# 02-Insence_interface.net
KiCad netlist of a schematic drawn in Altium Designer
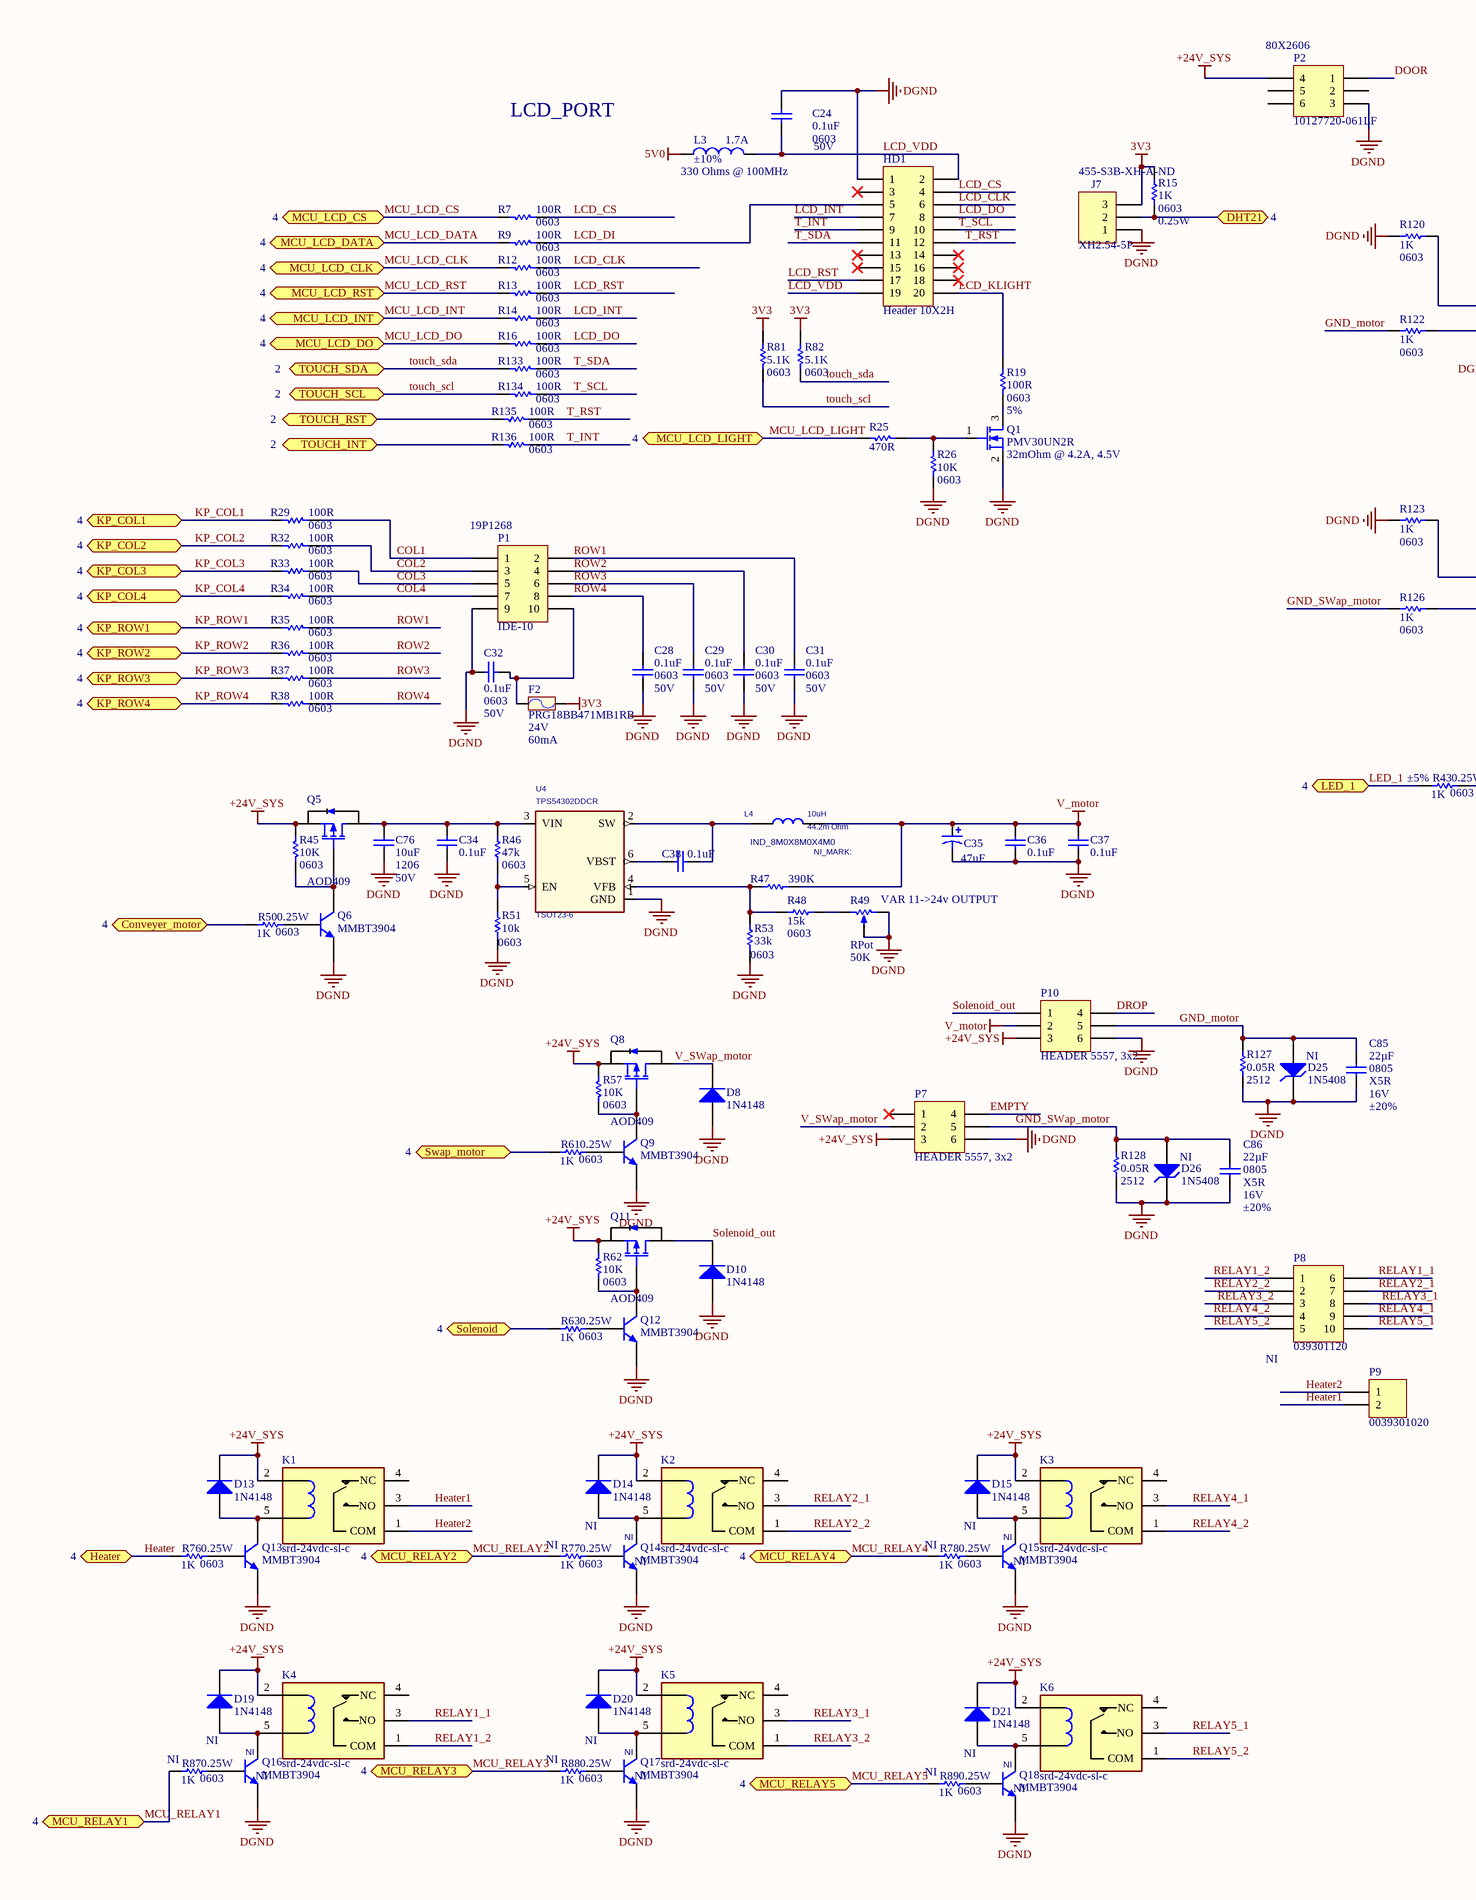
[diagram p0: 02-Insence_interface.SchDoc, left]
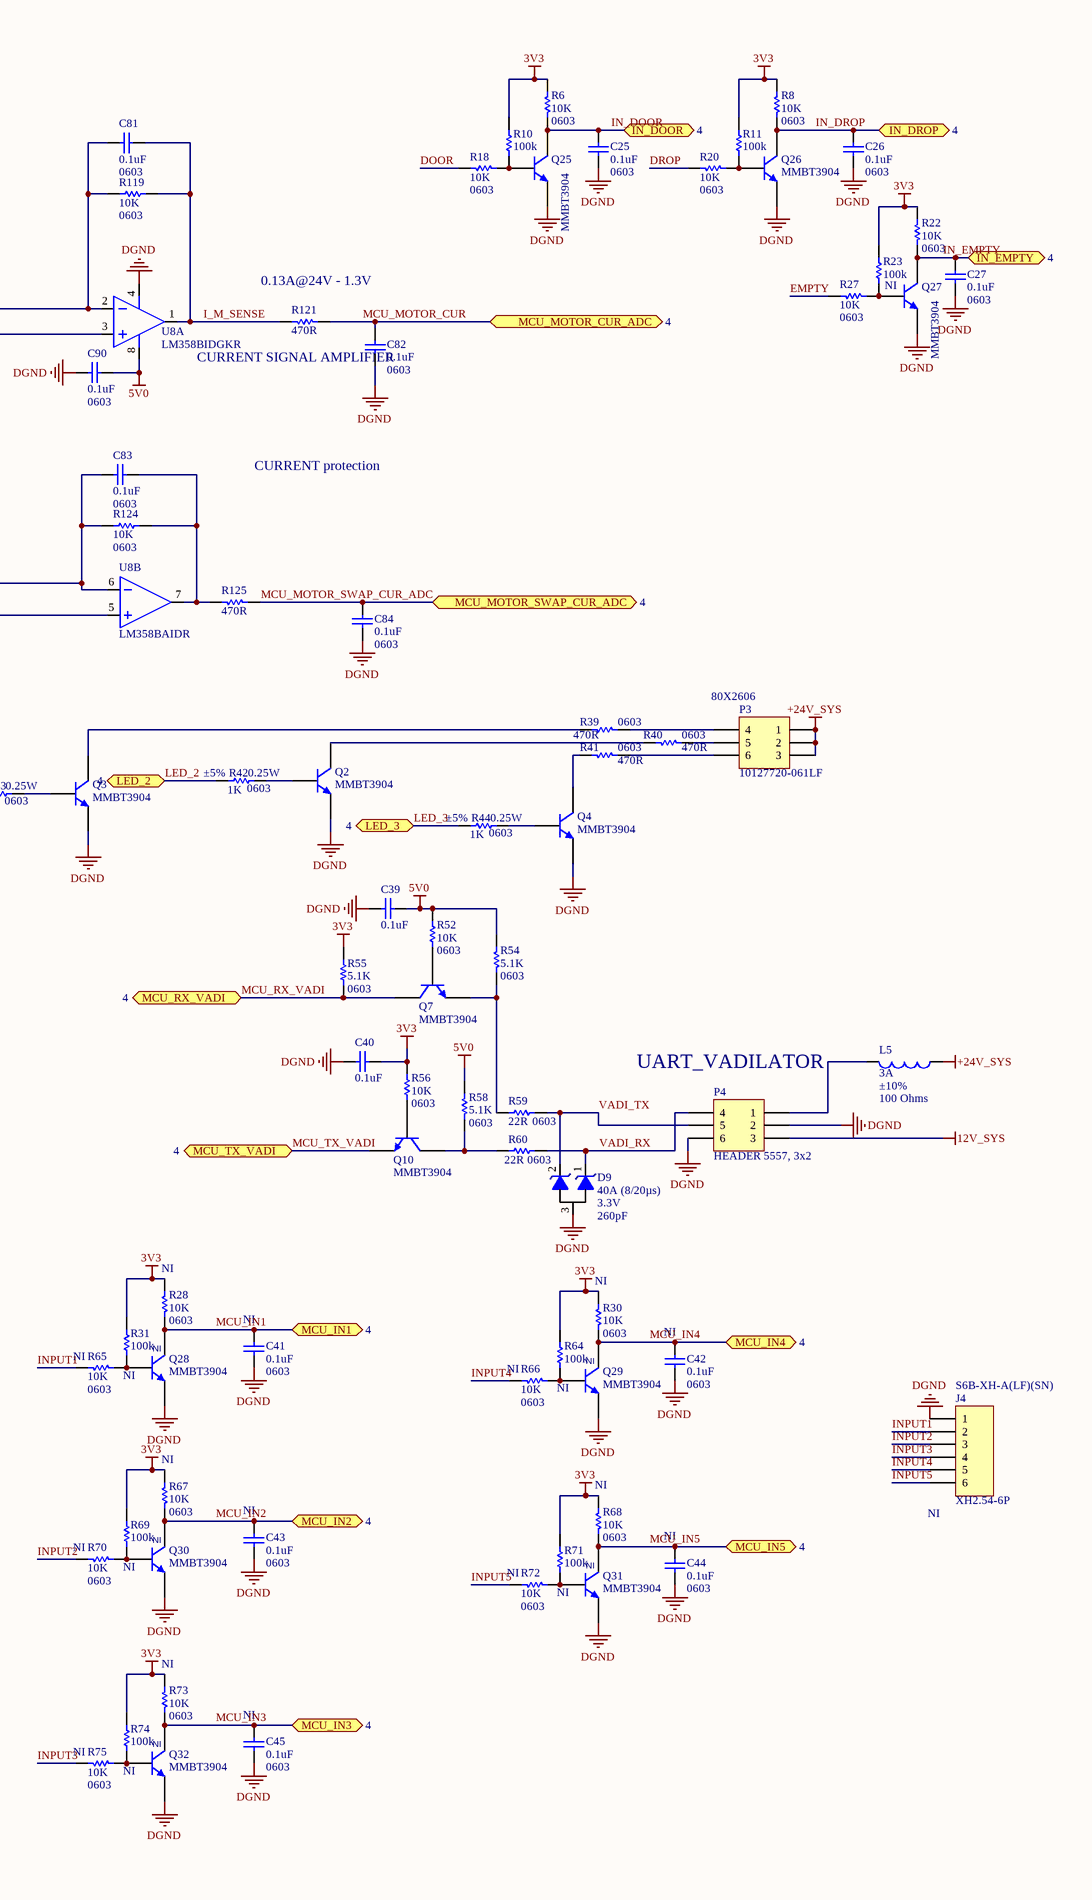
[diagram p1: 02-Insence_interface.SchDoc, right]

(export (version "E")
  (design (tool "Eeschema 10.0.6"))
  (components
    (comp (ref "C24")
      (value "0.1uF")
      (footprint "0603")
      (description "CAP CER 0.1UF 50V X7R 0603")
      (fields
        (field (name "MANUFACTURER1_PART#") "CL10B104KB8NNNC")
        (field (name "VOLTAGE") "50V")
        (field (name "TOLERANCE") "±10%")
      )
      (libsource (lib "thuvien") (part "Cap_0.1uF"))
    )
    (comp (ref "C25")
      (value "0.1uF")
      (footprint "0603")
      (description "CAP CER 0.1UF 50V X7R 0603")
      (fields (field (name "VOLTAGE") "50V") (field (name "TOLERANCE") "±10%"))
      (libsource (lib "Slider") (part "Cap"))
    )
    (comp (ref "C26")
      (value "0.1uF")
      (footprint "0603")
      (description "CAP CER 0.1UF 50V X7R 0603")
      (fields (field (name "VOLTAGE") "50V") (field (name "TOLERANCE") "±10%"))
      (libsource (lib "Slider") (part "Cap"))
    )
    (comp (ref "C27")
      (value "0.1uF")
      (footprint "0603")
      (description "CAP CER 0.1UF 50V X7R 0603")
      (fields (field (name "VOLTAGE") "50V") (field (name "TOLERANCE") "±10%"))
      (libsource (lib "Slider") (part "Cap"))
    )
    (comp (ref "C28")
      (value "0.1uF")
      (footprint "0603")
      (description "CAP CER 0.1UF 50V X7R 0603")
      (fields
        (field (name "MANUFACTURER1_PART#") "CL10B104KB8NNNC")
        (field (name "VOLTAGE") "50V")
        (field (name "TOLERANCE") "±10%")
      )
      (libsource (lib "thuvien") (part "Cap_0.1uF"))
    )
    (comp (ref "C29")
      (value "0.1uF")
      (footprint "0603")
      (description "CAP CER 0.1UF 50V X7R 0603")
      (fields
        (field (name "MANUFACTURER1_PART#") "CL10B104KB8NNNC")
        (field (name "VOLTAGE") "50V")
        (field (name "TOLERANCE") "±10%")
      )
      (libsource (lib "thuvien") (part "Cap_0.1uF"))
    )
    (comp (ref "C30")
      (value "0.1uF")
      (footprint "0603")
      (description "CAP CER 0.1UF 50V X7R 0603")
      (fields
        (field (name "MANUFACTURER1_PART#") "CL10B104KB8NNNC")
        (field (name "VOLTAGE") "50V")
        (field (name "TOLERANCE") "±10%")
      )
      (libsource (lib "thuvien") (part "Cap_0.1uF"))
    )
    (comp (ref "C31")
      (value "0.1uF")
      (footprint "0603")
      (description "CAP CER 0.1UF 50V X7R 0603")
      (fields
        (field (name "MANUFACTURER1_PART#") "CL10B104KB8NNNC")
        (field (name "VOLTAGE") "50V")
        (field (name "TOLERANCE") "±10%")
      )
      (libsource (lib "thuvien") (part "Cap_0.1uF"))
    )
    (comp (ref "C32")
      (value "0.1uF")
      (footprint "0603")
      (description "CAP CER 0.1UF 50V X7R 0603")
      (fields
        (field (name "MANUFACTURER1_PART#") "CL10B104KB8NNNC")
        (field (name "VOLTAGE") "50V")
        (field (name "TOLERANCE") "±10%")
      )
      (libsource (lib "thuvien") (part "Cap_0.1uF"))
    )
    (comp (ref "C34")
      (value "Cap")
      (footprint "0805")
      (description "CAP CER 0.1UF 50V X7R 0603")
      (fields
        (field (name "=VALUE") "0.1uF")
        (field (name "MANUFACTURER1_PART#") "CL10B104KB8NNNC")
        (field (name "PUBLISHER") "Altium Limited")
      )
      (libsource (lib "Miscellaneous Devices") (part "Cap"))
    )
    (comp (ref "C35")
      (value "47uF")
      (footprint "CAP ALUM SMD-D Package 6.3x5.4mm")
      (description "CAP ALUM 47UF 20% 35V SMD")
      (fields
        (field (name "MANUFACTURER1_PART#") "UUR1V470MCL6GS")
        (field (name "MANUFACTURER2_PART#") "EDK476M035A9GAA")
      )
      (libsource (lib "My Library") (part "Cap TANTAN 47UF35V2917"))
    )
    (comp (ref "C36")
      (value "Cap")
      (footprint "0805")
      (description "cap,0805,0.1uF,50V")
      (fields (field (name "=VALUE") "0.1uF") (field (name "PUBLISHER") "Altium Limited"))
      (libsource (lib "Miscellaneous Devices") (part "Cap"))
    )
    (comp (ref "C37")
      (value "Cap")
      (footprint "0805")
      (description "cap,0805,0.1uF,50V")
      (fields (field (name "=VALUE") "0.1uF") (field (name "PUBLISHER") "Altium Limited"))
      (libsource (lib "Miscellaneous Devices") (part "Cap"))
    )
    (comp (ref "C38")
      (value "Cap")
      (footprint "cap 0603")
      (description "CAP CER 0.1UF 50V X7R 0603")
      (fields
        (field (name "=VALUE") "0.1uF")
        (field (name "MANUFACTURER1_PART#") "CL10B104KB8NNNC")
        (field (name "PUBLISHER") "Altium Limited")
      )
      (libsource (lib "Miscellaneous Devices") (part "Cap"))
    )
    (comp (ref "C39")
      (value "0.1uF")
      (footprint "CAP 0603")
      (description "CAP CER 0.1UF 50V X7R 0603")
      (fields (field (name "VOLTAGE") "50V") (field (name "TOLERANCE") "±10%"))
      (libsource (lib "Slider") (part "Cap"))
    )
    (comp (ref "C40")
      (value "0.1uF")
      (footprint "CAP 0603")
      (description "CAP CER 0.1UF 50V X7R 0603")
      (fields (field (name "VOLTAGE") "50V") (field (name "TOLERANCE") "±10%"))
      (libsource (lib "Slider") (part "Cap"))
    )
    (comp (ref "C41")
      (value "0.1uF")
      (footprint "0603")
      (description "CAP CER 0.1UF 50V X7R 0603")
      (fields (field (name "NI_MARK") "NI") (field (name "VOLTAGE") "50V") (field (name "TOLERANCE") "±10%"))
      (libsource (lib "Slider") (part "Cap"))
    )
    (comp (ref "C42")
      (value "0.1uF")
      (footprint "0603")
      (description "CAP CER 0.1UF 50V X7R 0603")
      (fields (field (name "NI_MARK") "NI") (field (name "VOLTAGE") "50V") (field (name "TOLERANCE") "±10%"))
      (libsource (lib "Slider") (part "Cap"))
    )
    (comp (ref "C43")
      (value "0.1uF")
      (footprint "0603")
      (description "CAP CER 0.1UF 50V X7R 0603")
      (fields (field (name "NI_MARK") "NI") (field (name "VOLTAGE") "50V") (field (name "TOLERANCE") "±10%"))
      (libsource (lib "Slider") (part "Cap"))
    )
    (comp (ref "C44")
      (value "0.1uF")
      (footprint "0603")
      (description "CAP CER 0.1UF 50V X7R 0603")
      (fields (field (name "NI_MARK") "NI") (field (name "VOLTAGE") "50V") (field (name "TOLERANCE") "±10%"))
      (libsource (lib "Slider") (part "Cap"))
    )
    (comp (ref "C45")
      (value "0.1uF")
      (footprint "0603")
      (description "CAP CER 0.1UF 50V X7R 0603")
      (fields (field (name "NI_MARK") "NI") (field (name "VOLTAGE") "50V") (field (name "TOLERANCE") "±10%"))
      (libsource (lib "Slider") (part "Cap"))
    )
    (comp (ref "C76")
      (value "10uF")
      (footprint "1206")
      (description "CAP CER 10UF 50V X5R 1206")
      (fields
        (field (name "VOLTAGE") "50V")
        (field (name "TOLERANCE") "±10%")
        (field (name "MANUFACTURER1_PART#") "CL31A106MBHNNNE")
      )
      (libsource (lib "Slider") (part "Cap"))
    )
    (comp (ref "C81")
      (value "0.1uF")
      (footprint "0603")
      (description "CAP CER 0.1UF 50V X7R 0603")
      (fields (field (name "VOLTAGE") "50V") (field (name "TOLERANCE") "±10%"))
      (libsource (lib "Slider") (part "Cap"))
    )
    (comp (ref "C82")
      (value "0.1uF")
      (footprint "0603")
      (description "CAP CER 0.1UF 50V X7R 0603")
      (fields (field (name "VOLTAGE") "50V") (field (name "TOLERANCE") "±10%"))
      (libsource (lib "Slider") (part "Cap"))
    )
    (comp (ref "C83")
      (value "0.1uF")
      (footprint "0603")
      (description "CAP CER 0.1UF 50V X7R 0603")
      (fields (field (name "VOLTAGE") "50V") (field (name "TOLERANCE") "±10%"))
      (libsource (lib "Slider") (part "Cap"))
    )
    (comp (ref "C84")
      (value "0.1uF")
      (footprint "0603")
      (description "CAP CER 0.1UF 50V X7R 0603")
      (fields (field (name "VOLTAGE") "50V") (field (name "TOLERANCE") "±10%"))
      (libsource (lib "Slider") (part "Cap"))
    )
    (comp (ref "C85")
      (value "22µF")
      (footprint "CAP 0805")
      (description "CAP CER 22UF 16V X5R 0805")
      (fields
        (field (name "MANUFACTURER1_PART#") "CL21A226MOCLRNC")
        (field (name "MANUFACTURER2_PART#") "LMK212BBJ226MG-T")
        (field (name "PACKAGE") "0805")
        (field (name "VOLTAGE") "16V")
        (field (name "TOLERANCE") "±20%")
        (field (name "MATERIAL") "X5R")
      )
      (libsource (lib "Full") (part "Cap-NP-100"))
    )
    (comp (ref "C86")
      (value "22µF")
      (footprint "CAP 0805")
      (description "CAP CER 22UF 16V X5R 0805")
      (fields
        (field (name "MANUFACTURER1_PART#") "CL21A226MOCLRNC")
        (field (name "MANUFACTURER2_PART#") "LMK212BBJ226MG-T")
        (field (name "PACKAGE") "0805")
        (field (name "VOLTAGE") "16V")
        (field (name "TOLERANCE") "±20%")
        (field (name "MATERIAL") "X5R")
      )
      (libsource (lib "Full") (part "Cap-NP-100"))
    )
    (comp (ref "C90")
      (value "0.1uF")
      (footprint "0603")
      (description "CAP CER 0.1UF 50V X7R 0603")
      (fields (field (name "VOLTAGE") "50V") (field (name "TOLERANCE") "±10%"))
      (libsource (lib "Slider") (part "Cap"))
    )
    (comp (ref "D8")
      (value "1N4148")
      (footprint "diode_1206")
      (description "DIODE GP 100V 300MA SOD123 10K")
      (fields
        (field (name "MANUFACTURER1_PART#") "1N4148WQ-13-F")
        (field (name "PUBLISHER") "Altium Limited")
      )
      (libsource (lib "Miscellaneous Devices") (part "Diode"))
    )
    (comp (ref "D9")
      (value "SM3.3H-TP")
      (footprint "SOT-23-3")
      (description "3.3V, ESD PROTECTION DEVICES, SO")
      (fields
        (field (name "CURRENT") "40A (8/20µs)")
        (field (name "MANUFACTURER2_PART#") "GSOT03C-E3-08")
        (field (name "POWER") "500W")
        (field (name "VOLTAGE") "3.3V")
        (field (name "JUNCTION CAPACITANCE") "260pF")
      )
      (libsource (lib "My Library") (part "TVS_DUAL_3V3_SOT23"))
    )
    (comp (ref "D10")
      (value "1N4148")
      (footprint "diode_1206")
      (description "DIODE GP 100V 300MA SOD123 10K")
      (fields
        (field (name "MANUFACTURER1_PART#") "1N4148WQ-13-F")
        (field (name "PUBLISHER") "Altium Limited")
      )
      (libsource (lib "Miscellaneous Devices") (part "Diode"))
    )
    (comp (ref "D13")
      (value "1N4148")
      (footprint "diode_1206")
      (description "DIODE GP 100V 300MA SOD123 10K")
      (fields
        (field (name "MANUFACTURER1_PART#") "1N4148WQ-13-F")
        (field (name "PUBLISHER") "Altium Limited")
      )
      (libsource (lib "Miscellaneous Devices") (part "Diode"))
    )
    (comp (ref "D14")
      (value "1N4148")
      (footprint "diode_1206")
      (description "DIODE GP 100V 300MA SOD123 10K")
      (fields
        (field (name "MANUFACTURER1_PART#") "1N4148WQ-13-F")
        (field (name "NI_MARK") "NI")
        (field (name "PUBLISHER") "Altium Limited")
      )
      (libsource (lib "Miscellaneous Devices") (part "Diode"))
    )
    (comp (ref "D15")
      (value "1N4148")
      (footprint "diode_1206")
      (description "DIODE GP 100V 300MA SOD123 10K")
      (fields
        (field (name "MANUFACTURER1_PART#") "1N4148WQ-13-F")
        (field (name "NI_MARK") "NI")
        (field (name "PUBLISHER") "Altium Limited")
      )
      (libsource (lib "Miscellaneous Devices") (part "Diode"))
    )
    (comp (ref "D19")
      (value "1N4148")
      (footprint "diode_1206")
      (description "DIODE GP 100V 300MA SOD123 10K")
      (fields
        (field (name "MANUFACTURER1_PART#") "1N4148WQ-13-F")
        (field (name "NI_MARK") "NI")
        (field (name "PUBLISHER") "Altium Limited")
      )
      (libsource (lib "Miscellaneous Devices") (part "Diode"))
    )
    (comp (ref "D20")
      (value "1N4148")
      (footprint "diode_1206")
      (description "DIODE GP 100V 300MA SOD123 10K")
      (fields
        (field (name "MANUFACTURER1_PART#") "1N4148WQ-13-F")
        (field (name "NI_MARK") "NI")
        (field (name "PUBLISHER") "Altium Limited")
      )
      (libsource (lib "Miscellaneous Devices") (part "Diode"))
    )
    (comp (ref "D21")
      (value "1N4148")
      (footprint "diode_1206")
      (description "DIODE GP 100V 300MA SOD123 10K")
      (fields
        (field (name "MANUFACTURER1_PART#") "1N4148WQ-13-F")
        (field (name "NI_MARK") "NI")
        (field (name "PUBLISHER") "Altium Limited")
      )
      (libsource (lib "Miscellaneous Devices") (part "Diode"))
    )
    (comp (ref "D25")
      (value "1N5408")
      (footprint "SMB")
      (description "TVS DIODE 30V 50.82V DO214AB")
      (fields (field (name "MANUFACTURER1_PART#") "S3MHE3_A/I") (field (name "NI_MARK") "NI"))
      (libsource (lib "My Library") (part "Diode Zener"))
    )
    (comp (ref "D26")
      (value "1N5408")
      (footprint "SMB")
      (description "TVS DIODE 30V 50.82V DO214AB")
      (fields (field (name "MANUFACTURER1_PART#") "S3MHE3_A/I") (field (name "NI_MARK") "NI"))
      (libsource (lib "My Library") (part "Diode Zener"))
    )
    (comp (ref "F2")
      (value "PRG18BB471MB1RB")
      (footprint "FB 0603")
      (description "PTC RESET FUSE 24V 10MA 0603")
      (fields (field (name "VOLTAGE - RATED") "24V") (field (name "CURRENT RATING (AMPS)") "60mA"))
      (libsource (lib "power acdc 12v 400mA V05") (part "0875.800MXEP"))
    )
    (comp (ref "HD1")
      (value "Header 10X2H")
      (footprint "IDE_20-RA")
      (description "CONN HEADER R/A 20POS 2.54MM")
      (fields (field (name "MANUFACTURER1_PART#") "61202021721") (field (name "PUBLISHER") "Altium Limited"))
      (libsource (lib "Miscellaneous Connectors") (part "Header 10X2H"))
    )
    (comp (ref "J4")
      (value "XH2.54-6P")
      (footprint "XH2.54-6P-RA")
      (description "CONN HEADER R/A 6POS 2.5MM")
      (fields
        (field (name "SUPPLIER PART NUMBER 1") "S6B-XH-A(LF)(SN)")
        (field (name "MANUFACTURER1_PART#") "S6B-XH-A")
        (field (name "NI_MARK") "NI")
        (field (name "PUBLISHER") "Altium Limited")
      )
      (libsource (lib "Miscellaneous Connectors") (part "Header 6"))
    )
    (comp (ref "J7")
      (value "XH2.54-5P")
      (footprint "XH2.54-3P-RA")
      (description "CONN HEADER R/A 3POS 2.5MM")
      (fields
        (field (name "SUPPLIER PART NUMBER 1") "455-S3B-XH-A-ND")
        (field (name "MANUFACTURER1_PART#") "S3B-XH-A")
        (field (name "PUBLISHER") "Altium Limited")
      )
      (libsource (lib "Miscellaneous Connectors") (part "Header 3"))
    )
    (comp (ref "K1")
      (value "srd-24vdc-sl-c")
      (footprint "Hiendv:srd24vdcslc")
      (description "Relay 24V 10A 5 PIN")
      (libsource (lib "lib") (part "srd-24vdc-sl-c"))
    )
    (comp (ref "K2")
      (value "srd-24vdc-sl-c")
      (footprint "Hiendv:srd24vdcslc")
      (description "Relay 24V 10A 5 PIN")
      (fields (field (name "NI_MARK") "NI"))
      (libsource (lib "lib") (part "srd-24vdc-sl-c"))
    )
    (comp (ref "K3")
      (value "srd-24vdc-sl-c")
      (footprint "Hiendv:srd24vdcslc")
      (description "Relay 24V 10A 5 PIN")
      (fields (field (name "NI_MARK") "NI"))
      (libsource (lib "lib") (part "srd-24vdc-sl-c"))
    )
    (comp (ref "K4")
      (value "srd-24vdc-sl-c")
      (footprint "Hiendv:srd24vdcslc")
      (description "Relay 24V 10A 5 PIN")
      (fields (field (name "NI_MARK") "NI"))
      (libsource (lib "lib") (part "srd-24vdc-sl-c"))
    )
    (comp (ref "K5")
      (value "srd-24vdc-sl-c")
      (footprint "Hiendv:srd24vdcslc")
      (description "Relay 24V 10A 5 PIN")
      (fields (field (name "NI_MARK") "NI"))
      (libsource (lib "lib") (part "srd-24vdc-sl-c"))
    )
    (comp (ref "K6")
      (value "srd-24vdc-sl-c")
      (footprint "Hiendv:srd24vdcslc")
      (description "Relay 24V 10A 5 PIN")
      (fields (field (name "NI_MARK") "NI"))
      (libsource (lib "lib") (part "srd-24vdc-sl-c"))
    )
    (comp (ref "L3")
      (value "330 Ohms @ 100MHz")
      (footprint "FB 0603")
      (description "FERRITE BEAD 330 OHM 0603 1LN")
      (fields
        (field (name "MANUFACTURER1_PART#") "MPZ1608S331ATA00")
        (field (name "MANUFACTURER2_PART#") "BLM18KG331SN1D")
        (field (name "CURRENT") "1.7A")
        (field (name "TOLERANCE") "±10%")
      )
      (libsource (lib "Full") (part "inductor 2.2uF"))
    )
    (comp (ref "L4")
      (value "10uH")
      (footprint "IND 8x8MM")
      (description "IND-SMD;10uH,20%,8x8x4mm,3.1A,44.2mOHM")
      (fields
        (field (name "PACKAGE") "IND_8M0X8M0X4M0")
        (field (name "TOLERANCE") "20%")
        (field (name "MFG1_PART#") "NR8040T100M")
        (field (name "DCR") "44.2m Ohm")
        (field (name "BY") "VINFAST_RD")
      )
      (libsource (lib "*") (part "IND_10uH_3.1A_44.2mOhm_8MX8MX4M"))
    )
    (comp (ref "L5")
      (value "100 Ohms")
      (footprint "FB 0603")
      (description "FERRITE BEAD 100 OHM 0603 1LN")
      (fields
        (field (name "MANUFACTURER1_PART#") "MPZ1608S101ATAH0")
        (field (name "MANUFACTURER2_PART#") "BLM18KG101TN1D")
        (field (name "CURRENT") "3A")
        (field (name "TOLERANCE") "±10%")
      )
      (libsource (lib "Full") (part "inductor 2.2uF"))
    )
    (comp (ref "P1")
      (value "IDE-10")
      (footprint "IDE-10-RA")
      (description "CONN HEADER R/A 10POS 2.54MM")
      (fields
        (field (name "MANUFACTURER1_PART#") "61201021721")
        (field (name "SUPPLIER PART NUMBER 1") "19P1268")
      )
      (libsource (lib "My Library") (part "IDE10"))
    )
    (comp (ref "P2")
      (value "10127720-061LF")
      (footprint "PHM-3x2H 3.0 - RA")
      (description "Header, 3-Pin, Dual row")
      (fields (field (name "SUPPLIER PART NUMBER 1") "80X2606") (field (name "PUBLISHER") "Altium Limited"))
      (libsource (lib "") (part "Header 3X2A_1"))
    )
    (comp (ref "P3")
      (value "10127720-061LF")
      (footprint "PHM-3x2H 3.0 - RA")
      (description "Header, 3-Pin, Dual row")
      (fields (field (name "SUPPLIER PART NUMBER 1") "80X2606") (field (name "PUBLISHER") "Altium Limited"))
      (libsource (lib "") (part "Header 3X2A_1"))
    )
    (comp (ref "P4")
      (value "HEADER 5557, 3x2")
      (footprint "HDR2x3 4_2MM FEMALE TH RA")
      (description "CONN HEADER R/A 6POS 4.2MM")
      (fields (field (name "MANUFACTURER1_PART#") "0039301060") (field (name "PUBLISHER") "Altium Limited"))
      (libsource (lib "") (part "Header 3X2A_1"))
    )
    (comp (ref "P7")
      (value "HEADER 5557, 3x2")
      (footprint "HDR2x3 4_2MM FEMALE TH RA")
      (description "CONN HEADER R/A 6POS 4.2MM")
      (fields (field (name "MANUFACTURER1_PART#") "0039301060") (field (name "PUBLISHER") "Altium Limited"))
      (libsource (lib "Miscellaneous Connectors") (part "Header 3X2A"))
    )
    (comp (ref "P8")
      (value "039301120")
      (footprint "HDR2x5 4_2MM FEMALE TH RA")
      (description "CONN HEADER R/A 10POS 4.2MM")
      (fields (field (name "NI_MARK") "NI") (field (name "PUBLISHER") "Altium Limited"))
      (libsource (lib "Miscellaneous Connectors") (part "Header 5X2A"))
    )
    (comp (ref "P9")
      (value "0039301020")
      (footprint "HDR2x1 4_2MM FEMALE TH RA")
      (description "Header, 2-Pin, Right Angle")
      (fields (field (name "PUBLISHER") "Altium Limited"))
      (libsource (lib "Miscellaneous Connectors") (part "Header 2H"))
    )
    (comp (ref "P10")
      (value "HEADER 5557, 3x2")
      (footprint "HDR2x3 4_2MM FEMALE TH RA")
      (description "CONN HEADER R/A 6POS 4.2MM")
      (fields (field (name "MANUFACTURER1_PART#") "0039301060") (field (name "PUBLISHER") "Altium Limited"))
      (libsource (lib "Miscellaneous Connectors") (part "Header 3X2A"))
    )
    (comp (ref "Q1")
      (value "PMV30UN2R")
      (footprint "SOT-23-3")
      (description "MOSFET N-CH 20V 4.2A SOT23")
      (fields (field (name "RDSON") "32mOhm @ 4.2A, 4.5V"))
      (libsource (lib "VSM_SES-MAIN_REV04B") (part "Si2302DS"))
    )
    (comp (ref "Q2")
      (value "MMBT3904")
      (footprint "SOT-23")
      (description "NPN 200mA 40V 350mW SOT-23 Transistors")
      (libsource (lib "Miscellaneous Devices") (part "NPN"))
    )
    (comp (ref "Q3")
      (value "MMBT3904")
      (footprint "SOT-23")
      (description "NPN 200mA 40V 350mW SOT-23 Transistors")
      (libsource (lib "Miscellaneous Devices") (part "NPN"))
    )
    (comp (ref "Q4")
      (value "MMBT3904")
      (footprint "SOT-23")
      (description "NPN 200mA 40V 350mW SOT-23 Transistors")
      (libsource (lib "Miscellaneous Devices") (part "NPN"))
    )
    (comp (ref "Q5")
      (value "AOD409")
      (footprint "TO-252")
      (description "MOSFET P-CH 60V 26A TO252")
      (fields (field (name "PUBLISHER") "Altium Limited"))
      (libsource (lib "lib") (part "MOSFET-P"))
    )
    (comp (ref "Q6")
      (value "MMBT3904")
      (footprint "SOT-23")
      (description "NPN 200mA 40V 350mW SOT-23 Transistors")
      (libsource (lib "Miscellaneous Devices") (part "NPN"))
    )
    (comp (ref "Q7")
      (value "MMBT3904")
      (footprint "SOT-23")
      (description "NPN 200mA 40V 350mW SOT-23 Transistors")
      (libsource (lib "") (part "NPN_1"))
    )
    (comp (ref "Q8")
      (value "AOD409")
      (footprint "TO-252")
      (description "MOSFET P-CH 60V 26A TO252")
      (fields (field (name "PUBLISHER") "Altium Limited"))
      (libsource (lib "lib") (part "MOSFET-P"))
    )
    (comp (ref "Q9")
      (value "MMBT3904")
      (footprint "SOT-23")
      (description "NPN 200mA 40V 350mW SOT-23 Transistors")
      (libsource (lib "Miscellaneous Devices") (part "NPN"))
    )
    (comp (ref "Q10")
      (value "MMBT3904")
      (footprint "SOT-23")
      (description "NPN 200mA 40V 350mW SOT-23 Transistors")
      (libsource (lib "") (part "NPN_1"))
    )
    (comp (ref "Q11")
      (value "AOD409")
      (footprint "TO-252")
      (description "MOSFET P-CH 60V 26A TO252")
      (fields (field (name "PUBLISHER") "Altium Limited"))
      (libsource (lib "lib") (part "MOSFET-P"))
    )
    (comp (ref "Q12")
      (value "MMBT3904")
      (footprint "SOT-23")
      (description "NPN 200mA 40V 350mW SOT-23 Transistors")
      (libsource (lib "Miscellaneous Devices") (part "NPN"))
    )
    (comp (ref "Q13")
      (value "MMBT3904")
      (footprint "SOT-23")
      (description "NPN 200mA 40V 350mW SOT-23 Transistors")
      (libsource (lib "Miscellaneous Devices") (part "NPN"))
    )
    (comp (ref "Q14")
      (value "MMBT3904")
      (footprint "SOT-23")
      (description "NPN 200mA 40V 350mW SOT-23 Transistors")
      (fields (field (name "NI_MARK") "NI"))
      (libsource (lib "Miscellaneous Devices") (part "NPN"))
    )
    (comp (ref "Q15")
      (value "MMBT3904")
      (footprint "SOT-23")
      (description "NPN 200mA 40V 350mW SOT-23 Transistors")
      (fields (field (name "NI_MARK") "NI"))
      (libsource (lib "Miscellaneous Devices") (part "NPN"))
    )
    (comp (ref "Q16")
      (value "MMBT3904")
      (footprint "SOT-23")
      (description "NPN 200mA 40V 350mW SOT-23 Transistors")
      (fields (field (name "NI_MARK") "NI"))
      (libsource (lib "Miscellaneous Devices") (part "NPN"))
    )
    (comp (ref "Q17")
      (value "MMBT3904")
      (footprint "SOT-23")
      (description "NPN 200mA 40V 350mW SOT-23 Transistors")
      (fields (field (name "NI_MARK") "NI"))
      (libsource (lib "Miscellaneous Devices") (part "NPN"))
    )
    (comp (ref "Q18")
      (value "MMBT3904")
      (footprint "SOT-23")
      (description "NPN 200mA 40V 350mW SOT-23 Transistors")
      (fields (field (name "NI_MARK") "NI"))
      (libsource (lib "Miscellaneous Devices") (part "NPN"))
    )
    (comp (ref "Q25")
      (value "MMBT3904")
      (footprint "SOT-23")
      (description "NPN 200mA 40V 350mW SOT-23 Transistors")
      (libsource (lib "Miscellaneous Devices") (part "NPN"))
    )
    (comp (ref "Q26")
      (value "MMBT3904")
      (footprint "SOT-23")
      (description "NPN 200mA 40V 350mW SOT-23 Transistors")
      (libsource (lib "Miscellaneous Devices") (part "NPN"))
    )
    (comp (ref "Q27")
      (value "MMBT3904")
      (footprint "SOT-23")
      (description "NPN 200mA 40V 350mW SOT-23 Transistors")
      (libsource (lib "Miscellaneous Devices") (part "NPN"))
    )
    (comp (ref "Q28")
      (value "MMBT3904")
      (footprint "SOT-23")
      (description "NPN 200mA 40V 350mW SOT-23 Transistors")
      (fields (field (name "NI_MARK") "NI"))
      (libsource (lib "Miscellaneous Devices") (part "NPN"))
    )
    (comp (ref "Q29")
      (value "MMBT3904")
      (footprint "SOT-23")
      (description "NPN 200mA 40V 350mW SOT-23 Transistors")
      (fields (field (name "NI_MARK") "NI"))
      (libsource (lib "Miscellaneous Devices") (part "NPN"))
    )
    (comp (ref "Q30")
      (value "MMBT3904")
      (footprint "SOT-23")
      (description "NPN 200mA 40V 350mW SOT-23 Transistors")
      (fields (field (name "NI_MARK") "NI"))
      (libsource (lib "Miscellaneous Devices") (part "NPN"))
    )
    (comp (ref "Q31")
      (value "MMBT3904")
      (footprint "SOT-23")
      (description "NPN 200mA 40V 350mW SOT-23 Transistors")
      (fields (field (name "NI_MARK") "NI"))
      (libsource (lib "Miscellaneous Devices") (part "NPN"))
    )
    (comp (ref "Q32")
      (value "MMBT3904")
      (footprint "SOT-23")
      (description "NPN 200mA 40V 350mW SOT-23 Transistors")
      (fields (field (name "NI_MARK") "NI"))
      (libsource (lib "Miscellaneous Devices") (part "NPN"))
    )
    (comp (ref "R6")
      (value "10K")
      (footprint "res 0603")
      (description "RES SMD,10K OHM 5% 1/10W 0603")
      (fields
        (field (name "MANUFACTURER1_PART#") "RMCF0603JT10K0")
        (field (name "MANUFACTURER2_PART#") "R0603J10KKDX")
        (field (name "PCB FOOTPRINT") "0603")
      )
      (libsource (lib "altium-import") (part "root_3_mirrored_Res0.3_"))
    )
    (comp (ref "R7")
      (value "100R")
      (footprint "res 0603")
      (description "RES 100 OHM 5% 1/10W 0603")
      (fields (field (name "MANUFACTURER1_PART#") "RMCF0603JG100R") (field (name "PCB_ FOOTPRINT") "0603"))
      (libsource (lib "thuvien") (part "RES 120 OHM 5% 1/10W 0603"))
    )
    (comp (ref "R8")
      (value "10K")
      (footprint "res 0603")
      (description "RES SMD,10K OHM 5% 1/10W 0603")
      (fields
        (field (name "MANUFACTURER1_PART#") "RMCF0603JT10K0")
        (field (name "MANUFACTURER2_PART#") "R0603J10KKDX")
        (field (name "PCB FOOTPRINT") "0603")
      )
      (libsource (lib "altium-import") (part "root_3_mirrored_Res0.3_"))
    )
    (comp (ref "R9")
      (value "100R")
      (footprint "res 0603")
      (description "RES 100 OHM 5% 1/10W 0603")
      (fields (field (name "MANUFACTURER1_PART#") "RMCF0603JG100R") (field (name "PCB_ FOOTPRINT") "0603"))
      (libsource (lib "thuvien") (part "RES 120 OHM 5% 1/10W 0603"))
    )
    (comp (ref "R10")
      (value "100k")
      (footprint "RES 0603")
      (description "RES 100K OHM 1% 1/10W 0603")
      (fields
        (field (name "MANUFACTURER1_PART#") "RMCF0603FT100K")
        (field (name "Comment") "100k, 0603")
        (field (name "PUBLISHER") "Altium Limited")
      )
      (libsource (lib "Miscellaneous Devices") (part "Res1"))
    )
    (comp (ref "R11")
      (value "100k")
      (footprint "RES 0603")
      (description "RES 100K OHM 1% 1/10W 0603")
      (fields
        (field (name "MANUFACTURER1_PART#") "RMCF0603FT100K")
        (field (name "Comment") "100k, 0603")
        (field (name "PUBLISHER") "Altium Limited")
      )
      (libsource (lib "Miscellaneous Devices") (part "Res1"))
    )
    (comp (ref "R12")
      (value "100R")
      (footprint "res 0603")
      (description "RES 100 OHM 5% 1/10W 0603")
      (fields (field (name "MANUFACTURER1_PART#") "RMCF0603JG100R") (field (name "PCB_ FOOTPRINT") "0603"))
      (libsource (lib "thuvien") (part "RES 120 OHM 5% 1/10W 0603"))
    )
    (comp (ref "R13")
      (value "100R")
      (footprint "res 0603")
      (description "RES 100 OHM 5% 1/10W 0603")
      (fields (field (name "MANUFACTURER1_PART#") "RMCF0603JG100R") (field (name "PCB_ FOOTPRINT") "0603"))
      (libsource (lib "thuvien") (part "RES 120 OHM 5% 1/10W 0603"))
    )
    (comp (ref "R14")
      (value "100R")
      (footprint "res 0603")
      (description "RES 100 OHM 5% 1/10W 0603")
      (fields (field (name "MANUFACTURER1_PART#") "RMCF0603JG100R") (field (name "PCB_ FOOTPRINT") "0603"))
      (libsource (lib "thuvien") (part "RES 120 OHM 5% 1/10W 0603"))
    )
    (comp (ref "R15")
      (value "1K")
      (footprint "res 0603")
      (description "RES SMD,1K OHM,5%,1/10W,0603")
      (fields
        (field (name "MANUFACTURER1_PART#") "RMCF06031K00JNEAC")
        (field (name "MANUFACTURER2_PART#") "R0603J1KTG")
        (field (name "PCB FOOTPRINT") "0603")
        (field (name "POWER") "0.25W")
      )
      (libsource (lib "Full") (part "Res0.3"))
    )
    (comp (ref "R16")
      (value "100R")
      (footprint "res 0603")
      (description "RES 100 OHM 5% 1/10W 0603")
      (fields (field (name "MANUFACTURER1_PART#") "RMCF0603JG100R") (field (name "PCB_ FOOTPRINT") "0603"))
      (libsource (lib "thuvien") (part "RES 120 OHM 5% 1/10W 0603"))
    )
    (comp (ref "R18")
      (value "10K")
      (footprint "res 0603")
      (description "RES SMD,10K OHM 5% 1/10W 0603")
      (fields
        (field (name "MANUFACTURER1_PART#") "RMCF0603JT10K0")
        (field (name "MANUFACTURER2_PART#") "R0603J10KKDX")
        (field (name "PCB FOOTPRINT") "0603")
      )
      (libsource (lib "altium-import") (part "root_2_mirrored_Res0.3_"))
    )
    (comp (ref "R19")
      (value "100R")
      (footprint "res 0603")
      (description "RES 100 OHM 5% 1/10W 0603")
      (fields
        (field (name "MANUFACTURER1_PART#") "RMCF0603JG100R")
        (field (name "PCB_ FOOTPRINT") "0603")
        (field (name "TOLERANCE") "5%")
      )
      (libsource (lib "thuvien") (part "RES 120 OHM 5% 1/10W 0603"))
    )
    (comp (ref "R20")
      (value "10K")
      (footprint "res 0603")
      (description "RES SMD,10K OHM 5% 1/10W 0603")
      (fields
        (field (name "MANUFACTURER1_PART#") "RMCF0603JT10K0")
        (field (name "MANUFACTURER2_PART#") "R0603J10KKDX")
        (field (name "PCB FOOTPRINT") "0603")
      )
      (libsource (lib "altium-import") (part "root_2_mirrored_Res0.3_"))
    )
    (comp (ref "R22")
      (value "10K")
      (footprint "res 0603")
      (description "RES SMD,10K OHM 5% 1/10W 0603")
      (fields
        (field (name "MANUFACTURER1_PART#") "RMCF0603JT10K0")
        (field (name "MANUFACTURER2_PART#") "R0603J10KKDX")
        (field (name "PCB FOOTPRINT") "0603")
      )
      (libsource (lib "altium-import") (part "root_3_mirrored_Res0.3_"))
    )
    (comp (ref "R23")
      (value "100k")
      (footprint "RES 0603")
      (description "RES 100K OHM 1% 1/10W 0603")
      (fields
        (field (name "MANUFACTURER1_PART#") "RMCF0603FT100K")
        (field (name "ASSEMBLY") "NI")
        (field (name "Comment") "100k, 0603")
        (field (name "PUBLISHER") "Altium Limited")
      )
      (libsource (lib "Miscellaneous Devices") (part "Res1"))
    )
    (comp (ref "R25")
      (value "470R")
      (footprint "res 0603")
      (description "RES SMD, 470 OHM 5% 1/8W 0603")
      (fields
        (field (name "MANUFACTURER1_PART#") "RK73B1JTTD471J")
        (field (name "MANUFACTURER2_PART#") "RMCF0603JT470R")
      )
      (libsource (lib "Full") (part "Res0.3"))
    )
    (comp (ref "R26")
      (value "10K")
      (footprint "res 0603")
      (description "RES SMD,10K OHM 5% 1/10W 0603")
      (fields
        (field (name "MANUFACTURER1_PART#") "RMCF0603JT10K0")
        (field (name "MANUFACTURER2_PART#") "R0603J10KKDX")
        (field (name "PCB FOOTPRINT") "0603")
      )
      (libsource (lib "altium-import") (part "root_3_mirrored_Res0.3_"))
    )
    (comp (ref "R27")
      (value "10K")
      (footprint "res 0603")
      (description "RES SMD,10K OHM 5% 1/10W 0603")
      (fields
        (field (name "MANUFACTURER1_PART#") "RMCF0603JT10K0")
        (field (name "MANUFACTURER2_PART#") "R0603J10KKDX")
        (field (name "PCB FOOTPRINT") "0603")
      )
      (libsource (lib "altium-import") (part "root_2_mirrored_Res0.3_"))
    )
    (comp (ref "R28")
      (value "10K")
      (footprint "res 0603")
      (description "RES SMD,10K OHM 5% 1/10W 0603")
      (fields
        (field (name "MANUFACTURER1_PART#") "RMCF0603JT10K0")
        (field (name "MANUFACTURER2_PART#") "R0603J10KKDX")
        (field (name "NI_MARK") "NI")
        (field (name "PCB FOOTPRINT") "0603")
      )
      (libsource (lib "altium-import") (part "root_3_mirrored_Res0.3_"))
    )
    (comp (ref "R29")
      (value "100R")
      (footprint "res 0603")
      (description "RES 100 OHM 5% 1/10W 0603")
      (fields (field (name "MANUFACTURER1_PART#") "RMCF0603JG100R") (field (name "PCB_ FOOTPRINT") "0603"))
      (libsource (lib "thuvien") (part "RES 120 OHM 5% 1/10W 0603"))
    )
    (comp (ref "R30")
      (value "10K")
      (footprint "res 0603")
      (description "RES SMD,10K OHM 5% 1/10W 0603")
      (fields
        (field (name "MANUFACTURER1_PART#") "RMCF0603JT10K0")
        (field (name "MANUFACTURER2_PART#") "R0603J10KKDX")
        (field (name "NI_MARK") "NI")
        (field (name "PCB FOOTPRINT") "0603")
      )
      (libsource (lib "altium-import") (part "root_3_mirrored_Res0.3_"))
    )
    (comp (ref "R31")
      (value "100k")
      (footprint "RES 0603")
      (description "RES 100K OHM 1% 1/10W 0603")
      (fields
        (field (name "MANUFACTURER1_PART#") "RMCF0603FT100K")
        (field (name "NI_MARK") "NI")
        (field (name "Comment") "100k, 0603")
        (field (name "PUBLISHER") "Altium Limited")
      )
      (libsource (lib "Miscellaneous Devices") (part "Res1"))
    )
    (comp (ref "R32")
      (value "100R")
      (footprint "res 0603")
      (description "RES 100 OHM 5% 1/10W 0603")
      (fields (field (name "MANUFACTURER1_PART#") "RMCF0603JG100R") (field (name "PCB_ FOOTPRINT") "0603"))
      (libsource (lib "thuvien") (part "RES 120 OHM 5% 1/10W 0603"))
    )
    (comp (ref "R33")
      (value "100R")
      (footprint "res 0603")
      (description "RES 100 OHM 5% 1/10W 0603")
      (fields (field (name "MANUFACTURER1_PART#") "RMCF0603JG100R") (field (name "PCB_ FOOTPRINT") "0603"))
      (libsource (lib "thuvien") (part "RES 120 OHM 5% 1/10W 0603"))
    )
    (comp (ref "R34")
      (value "100R")
      (footprint "res 0603")
      (description "RES 100 OHM 5% 1/10W 0603")
      (fields (field (name "MANUFACTURER1_PART#") "RMCF0603JG100R") (field (name "PCB_ FOOTPRINT") "0603"))
      (libsource (lib "thuvien") (part "RES 120 OHM 5% 1/10W 0603"))
    )
    (comp (ref "R35")
      (value "100R")
      (footprint "res 0603")
      (description "RES 100 OHM 5% 1/10W 0603")
      (fields (field (name "MANUFACTURER1_PART#") "RMCF0603JG100R") (field (name "PCB_ FOOTPRINT") "0603"))
      (libsource (lib "thuvien") (part "RES 120 OHM 5% 1/10W 0603"))
    )
    (comp (ref "R36")
      (value "100R")
      (footprint "res 0603")
      (description "RES 100 OHM 5% 1/10W 0603")
      (fields (field (name "MANUFACTURER1_PART#") "RMCF0603JG100R") (field (name "PCB_ FOOTPRINT") "0603"))
      (libsource (lib "thuvien") (part "RES 120 OHM 5% 1/10W 0603"))
    )
    (comp (ref "R37")
      (value "100R")
      (footprint "res 0603")
      (description "RES 100 OHM 5% 1/10W 0603")
      (fields (field (name "MANUFACTURER1_PART#") "RMCF0603JG100R") (field (name "PCB_ FOOTPRINT") "0603"))
      (libsource (lib "thuvien") (part "RES 120 OHM 5% 1/10W 0603"))
    )
    (comp (ref "R38")
      (value "100R")
      (footprint "res 0603")
      (description "RES 100 OHM 5% 1/10W 0603")
      (fields (field (name "MANUFACTURER1_PART#") "RMCF0603JG100R") (field (name "PCB_ FOOTPRINT") "0603"))
      (libsource (lib "thuvien") (part "RES 120 OHM 5% 1/10W 0603"))
    )
    (comp (ref "R39")
      (value "470R")
      (footprint "res 0603")
      (description "RES SMD, 470 OHM 5% 1/8W 0603")
      (fields
        (field (name "MANUFACTURER1_PART#") "RK73B1JTTD471J")
        (field (name "MANUFACTURER2_PART#") "RMCF0603JT470R")
        (field (name "PCB FOOTPRINT") "0603")
      )
      (libsource (lib "Full") (part "Res0.3"))
    )
    (comp (ref "R40")
      (value "470R")
      (footprint "res 0603")
      (description "RES SMD, 470 OHM 5% 1/8W 0603")
      (fields
        (field (name "MANUFACTURER1_PART#") "RK73B1JTTD471J")
        (field (name "MANUFACTURER2_PART#") "RMCF0603JT470R")
        (field (name "PCB FOOTPRINT") "0603")
      )
      (libsource (lib "Full") (part "Res0.3"))
    )
    (comp (ref "R41")
      (value "470R")
      (footprint "res 0603")
      (description "RES SMD, 470 OHM 5% 1/8W 0603")
      (fields
        (field (name "MANUFACTURER1_PART#") "RK73B1JTTD471J")
        (field (name "MANUFACTURER2_PART#") "RMCF0603JT470R")
        (field (name "PCB FOOTPRINT") "0603")
      )
      (libsource (lib "Full") (part "Res0.3"))
    )
    (comp (ref "R42")
      (value "1K")
      (footprint "res 0603")
      (description "RES SMD,1K OHM,5%,1/10W,0603")
      (fields
        (field (name "MANUFACTURER1_PART#") "RMCF06031K00JNEAC")
        (field (name "MANUFACTURER2_PART#") "R0603J1KTG")
        (field (name "PCB FOOTPRINT") "0603")
        (field (name "POWER") "0.25W")
        (field (name "TOLERANCE") "±5%")
      )
      (libsource (lib "Full") (part "Res0.3"))
    )
    (comp (ref "R43")
      (value "1K")
      (footprint "res 0603")
      (description "RES SMD,1K OHM,5%,1/10W,0603")
      (fields
        (field (name "MANUFACTURER1_PART#") "RMCF06031K00JNEAC")
        (field (name "MANUFACTURER2_PART#") "R0603J1KTG")
        (field (name "PCB FOOTPRINT") "0603")
        (field (name "POWER") "0.25W")
        (field (name "TOLERANCE") "±5%")
      )
      (libsource (lib "Full") (part "Res0.3"))
    )
    (comp (ref "R44")
      (value "1K")
      (footprint "res 0603")
      (description "RES SMD,1K OHM,5%,1/10W,0603")
      (fields
        (field (name "MANUFACTURER1_PART#") "RMCF06031K00JNEAC")
        (field (name "MANUFACTURER2_PART#") "R0603J1KTG")
        (field (name "PCB FOOTPRINT") "0603")
        (field (name "POWER") "0.25W")
        (field (name "TOLERANCE") "±5%")
      )
      (libsource (lib "Full") (part "Res0.3"))
    )
    (comp (ref "R45")
      (value "10K")
      (footprint "res 0603")
      (description "RES SMD,10K OHM 5% 1/10W 0603")
      (fields
        (field (name "MANUFACTURER1_PART#") "RMCF0603JT10K0")
        (field (name "MANUFACTURER2_PART#") "R0603J10KKDX")
        (field (name "PCB FOOTPRINT") "0603")
      )
      (libsource (lib "altium-import") (part "root_3_mirrored_Res0.3_"))
    )
    (comp (ref "R46")
      (value "47k")
      (footprint "0603")
      (description "RES 47K OHM 5% 1/10W 0603")
      (fields
        (field (name "MANUFACTURER1_PART#") "RMCF0603JT47K0")
        (field (name "Comment") "Res1")
        (field (name "PUBLISHER") "Altium Limited")
      )
      (libsource (lib "Miscellaneous Devices") (part "Res1"))
    )
    (comp (ref "R47")
      (value "390K")
      (footprint "res 0603")
      (description "RES 390K OHM 1% 1/10W 0603")
      (fields
        (field (name "MANUFACTURER1_PART#") "RC0603FR-07390KL")
        (field (name "Comment") "Res1")
        (field (name "PUBLISHER") "Altium Limited")
      )
      (libsource (lib "Miscellaneous Devices") (part "Res1"))
    )
    (comp (ref "R48")
      (value "15k")
      (footprint "0603")
      (description "RES SMD,15K OHM 5% 1/10W 0603")
      (fields
        (field (name "MANUFACTURER1_PART#") "RMCF0603JT15K0")
        (field (name "Comment") "Res1")
        (field (name "PUBLISHER") "Altium Limited")
      )
      (libsource (lib "Miscellaneous Devices") (part "Res1"))
    )
    (comp (ref "R49")
      (value "RPot")
      (footprint "R_POT_RA")
      (description "VR 3006P-1-503")
      (fields
        (field (name "ALTIUM_VALUE") "50K")
        (field (name "MANUFACTURER1_PART#") "3006P-1-503")
        (field (name "PUBLISHER") "Altium Limited")
      )
      (libsource (lib "Miscellaneous Devices") (part "RPot"))
    )
    (comp (ref "R50")
      (value "1K")
      (footprint "res 0603")
      (description "RES SMD,1K OHM,5%,1/10W,0603")
      (fields
        (field (name "MANUFACTURER1_PART#") "RMCF06031K00JNEAC")
        (field (name "MANUFACTURER2_PART#") "R0603J1KTG")
        (field (name "PCB FOOTPRINT") "0603")
        (field (name "POWER") "0.25W")
      )
      (libsource (lib "Full") (part "Res0.3"))
    )
    (comp (ref "R51")
      (value "10k")
      (footprint "0603")
      (description "RES SMD,10K OHM 5% 1/10W 0603")
      (fields
        (field (name "MANUFACTURER1_PART#") "RMCF0603JT10K0")
        (field (name "Comment") "Res1")
        (field (name "PUBLISHER") "Altium Limited")
      )
      (libsource (lib "Miscellaneous Devices") (part "Res1"))
    )
    (comp (ref "R52")
      (value "10K")
      (footprint "res 0603")
      (description "RES SMD,10K OHM 5% 1/10W 0603")
      (fields
        (field (name "MANUFACTURER1_PART#") "RMCF0603JT10K0")
        (field (name "MANUFACTURER2_PART#") "R0603J10KKDX")
        (field (name "PCB FOOTPRINT") "0603")
      )
      (libsource (lib "altium-import") (part "root_3_Res0.3_"))
    )
    (comp (ref "R53")
      (value "33k")
      (footprint "0603")
      (description "RES SMD,33K OHM 5% 1/10W 0603")
      (fields
        (field (name "MANUFACTURER1_PART#") "RMCF0603JT33K0")
        (field (name "Comment") "Res1")
        (field (name "PUBLISHER") "Altium Limited")
      )
      (libsource (lib "Miscellaneous Devices") (part "Res1"))
    )
    (comp (ref "R54")
      (value "5.1K")
      (footprint "res 0603")
      (description "RES SMD 5.1K OHM 1% 1/10W 0603")
      (fields (field (name "MANUFACTURER1_PART#") "RC0603FR-075K1L") (field (name "PCB FOOTPRINT") "0603"))
      (libsource (lib "Full") (part "Res0.3"))
    )
    (comp (ref "R55")
      (value "5.1K")
      (footprint "res 0603")
      (description "RES SMD 5.1K OHM 1% 1/10W 0603")
      (fields (field (name "MANUFACTURER1_PART#") "RC0603FR-075K1L") (field (name "PCB FOOTPRINT") "0603"))
      (libsource (lib "Full") (part "Res0.3"))
    )
    (comp (ref "R56")
      (value "10K")
      (footprint "res 0603")
      (description "RES SMD,10K OHM 5% 1/10W 0603")
      (fields
        (field (name "MANUFACTURER1_PART#") "RMCF0603JT10K0")
        (field (name "MANUFACTURER2_PART#") "R0603J10KKDX")
        (field (name "PCB FOOTPRINT") "0603")
      )
      (libsource (lib "altium-import") (part "root_3_Res0.3_"))
    )
    (comp (ref "R57")
      (value "10K")
      (footprint "res 0603")
      (description "RES SMD,10K OHM 5% 1/10W 0603")
      (fields
        (field (name "MANUFACTURER1_PART#") "RMCF0603JT10K0")
        (field (name "MANUFACTURER2_PART#") "R0603J10KKDX")
        (field (name "PCB FOOTPRINT") "0603")
      )
      (libsource (lib "altium-import") (part "root_3_mirrored_Res0.3_"))
    )
    (comp (ref "R58")
      (value "5.1K")
      (footprint "res 0603")
      (description "RES SMD 5.1K OHM 1% 1/10W 0603")
      (fields (field (name "MANUFACTURER1_PART#") "RC0603FR-075K1L") (field (name "PCB FOOTPRINT") "0603"))
      (libsource (lib "Full") (part "Res0.3"))
    )
    (comp (ref "R59")
      (value "22R")
      (footprint "res 0603")
      (description "RES 22 OHM 5% 1/10W 0603")
      (fields
        (field (name "MANUFACTURER1_PART#") "RC0603JR-0722RL")
        (field (name "MANUFACTURER2_PART#") "RMCF0603JT22R0")
        (field (name "PCB FOOTPRINT") "0603")
      )
      (libsource (lib "Full") (part "Res0.3"))
    )
    (comp (ref "R60")
      (value "22R")
      (footprint "res 0603")
      (description "RES 22 OHM 5% 1/10W 0603")
      (fields
        (field (name "MANUFACTURER1_PART#") "RC0603JR-0722RL")
        (field (name "MANUFACTURER2_PART#") "RMCF0603JT22R0")
        (field (name "PCB FOOTPRINT") "0603")
      )
      (libsource (lib "Full") (part "Res0.3"))
    )
    (comp (ref "R61")
      (value "1K")
      (footprint "res 0603")
      (description "RES SMD,1K OHM,5%,1/10W,0603")
      (fields
        (field (name "MANUFACTURER1_PART#") "RMCF06031K00JNEAC")
        (field (name "MANUFACTURER2_PART#") "R0603J1KTG")
        (field (name "PCB FOOTPRINT") "0603")
        (field (name "POWER") "0.25W")
      )
      (libsource (lib "Full") (part "Res0.3"))
    )
    (comp (ref "R62")
      (value "10K")
      (footprint "res 0603")
      (description "RES SMD,10K OHM 5% 1/10W 0603")
      (fields
        (field (name "MANUFACTURER1_PART#") "RMCF0603JT10K0")
        (field (name "MANUFACTURER2_PART#") "R0603J10KKDX")
        (field (name "PCB FOOTPRINT") "0603")
      )
      (libsource (lib "altium-import") (part "root_3_mirrored_Res0.3_"))
    )
    (comp (ref "R63")
      (value "1K")
      (footprint "res 0603")
      (description "RES SMD,1K OHM,5%,1/10W,0603")
      (fields
        (field (name "MANUFACTURER1_PART#") "RMCF06031K00JNEAC")
        (field (name "MANUFACTURER2_PART#") "R0603J1KTG")
        (field (name "PCB FOOTPRINT") "0603")
        (field (name "POWER") "0.25W")
      )
      (libsource (lib "Full") (part "Res0.3"))
    )
    (comp (ref "R64")
      (value "100k")
      (footprint "RES 0603")
      (description "RES 100K OHM 1% 1/10W 0603")
      (fields
        (field (name "MANUFACTURER1_PART#") "RMCF0603FT100K")
        (field (name "NI_MARK") "NI")
        (field (name "Comment") "100k, 0603")
        (field (name "PUBLISHER") "Altium Limited")
      )
      (libsource (lib "Miscellaneous Devices") (part "Res1"))
    )
    (comp (ref "R65")
      (value "10K")
      (footprint "res 0603")
      (description "RES SMD,10K OHM 5% 1/10W 0603")
      (fields
        (field (name "MANUFACTURER1_PART#") "RMCF0603JT10K0")
        (field (name "MANUFACTURER2_PART#") "R0603J10KKDX")
        (field (name "NI_MARK") "NI")
        (field (name "PCB FOOTPRINT") "0603")
      )
      (libsource (lib "altium-import") (part "root_2_mirrored_Res0.3_"))
    )
    (comp (ref "R66")
      (value "10K")
      (footprint "res 0603")
      (description "RES SMD,10K OHM 5% 1/10W 0603")
      (fields
        (field (name "MANUFACTURER1_PART#") "RMCF0603JT10K0")
        (field (name "MANUFACTURER2_PART#") "R0603J10KKDX")
        (field (name "NI_MARK") "NI")
        (field (name "PCB FOOTPRINT") "0603")
      )
      (libsource (lib "altium-import") (part "root_2_mirrored_Res0.3_"))
    )
    (comp (ref "R67")
      (value "10K")
      (footprint "res 0603")
      (description "RES SMD,10K OHM 5% 1/10W 0603")
      (fields
        (field (name "MANUFACTURER1_PART#") "RMCF0603JT10K0")
        (field (name "MANUFACTURER2_PART#") "R0603J10KKDX")
        (field (name "NI_MARK") "NI")
        (field (name "PCB FOOTPRINT") "0603")
      )
      (libsource (lib "altium-import") (part "root_3_mirrored_Res0.3_"))
    )
    (comp (ref "R68")
      (value "10K")
      (footprint "res 0603")
      (description "RES SMD,10K OHM 5% 1/10W 0603")
      (fields
        (field (name "MANUFACTURER1_PART#") "RMCF0603JT10K0")
        (field (name "MANUFACTURER2_PART#") "R0603J10KKDX")
        (field (name "NI_MARK") "NI")
        (field (name "PCB FOOTPRINT") "0603")
      )
      (libsource (lib "altium-import") (part "root_3_mirrored_Res0.3_"))
    )
    (comp (ref "R69")
      (value "100k")
      (footprint "RES 0603")
      (description "RES 100K OHM 1% 1/10W 0603")
      (fields
        (field (name "MANUFACTURER1_PART#") "RMCF0603FT100K")
        (field (name "NI_MARK") "NI")
        (field (name "Comment") "100k, 0603")
        (field (name "PUBLISHER") "Altium Limited")
      )
      (libsource (lib "Miscellaneous Devices") (part "Res1"))
    )
    (comp (ref "R70")
      (value "10K")
      (footprint "res 0603")
      (description "RES SMD,10K OHM 5% 1/10W 0603")
      (fields
        (field (name "MANUFACTURER1_PART#") "RMCF0603JT10K0")
        (field (name "MANUFACTURER2_PART#") "R0603J10KKDX")
        (field (name "NI_MARK") "NI")
        (field (name "PCB FOOTPRINT") "0603")
      )
      (libsource (lib "altium-import") (part "root_2_mirrored_Res0.3_"))
    )
    (comp (ref "R71")
      (value "100k")
      (footprint "RES 0603")
      (description "RES 100K OHM 1% 1/10W 0603")
      (fields
        (field (name "MANUFACTURER1_PART#") "RMCF0603FT100K")
        (field (name "NI_MARK") "NI")
        (field (name "Comment") "100k, 0603")
        (field (name "PUBLISHER") "Altium Limited")
      )
      (libsource (lib "Miscellaneous Devices") (part "Res1"))
    )
    (comp (ref "R72")
      (value "10K")
      (footprint "res 0603")
      (description "RES SMD,10K OHM 5% 1/10W 0603")
      (fields
        (field (name "MANUFACTURER1_PART#") "RMCF0603JT10K0")
        (field (name "MANUFACTURER2_PART#") "R0603J10KKDX")
        (field (name "NI_MARK") "NI")
        (field (name "PCB FOOTPRINT") "0603")
      )
      (libsource (lib "altium-import") (part "root_2_mirrored_Res0.3_"))
    )
    (comp (ref "R73")
      (value "10K")
      (footprint "res 0603")
      (description "RES SMD,10K OHM 5% 1/10W 0603")
      (fields
        (field (name "MANUFACTURER1_PART#") "RMCF0603JT10K0")
        (field (name "MANUFACTURER2_PART#") "R0603J10KKDX")
        (field (name "NI_MARK") "NI")
        (field (name "PCB FOOTPRINT") "0603")
      )
      (libsource (lib "altium-import") (part "root_3_mirrored_Res0.3_"))
    )
    (comp (ref "R74")
      (value "100k")
      (footprint "RES 0603")
      (description "RES 100K OHM 1% 1/10W 0603")
      (fields
        (field (name "MANUFACTURER1_PART#") "RMCF0603FT100K")
        (field (name "NI_MARK") "NI")
        (field (name "Comment") "100k, 0603")
        (field (name "PUBLISHER") "Altium Limited")
      )
      (libsource (lib "Miscellaneous Devices") (part "Res1"))
    )
    (comp (ref "R75")
      (value "10K")
      (footprint "res 0603")
      (description "RES SMD,10K OHM 5% 1/10W 0603")
      (fields
        (field (name "MANUFACTURER1_PART#") "RMCF0603JT10K0")
        (field (name "MANUFACTURER2_PART#") "R0603J10KKDX")
        (field (name "NI_MARK") "NI")
        (field (name "PCB FOOTPRINT") "0603")
      )
      (libsource (lib "altium-import") (part "root_2_mirrored_Res0.3_"))
    )
    (comp (ref "R76")
      (value "1K")
      (footprint "res 0603")
      (description "RES SMD,1K OHM,5%,1/10W,0603")
      (fields
        (field (name "MANUFACTURER1_PART#") "RMCF06031K00JNEAC")
        (field (name "MANUFACTURER2_PART#") "R0603J1KTG")
        (field (name "PCB FOOTPRINT") "0603")
        (field (name "POWER") "0.25W")
      )
      (libsource (lib "Full") (part "Res0.3"))
    )
    (comp (ref "R77")
      (value "1K")
      (footprint "res 0603")
      (description "RES SMD,1K OHM,5%,1/10W,0603")
      (fields
        (field (name "MANUFACTURER1_PART#") "RMCF06031K00JNEAC")
        (field (name "MANUFACTURER2_PART#") "R0603J1KTG")
        (field (name "NI_MARK") "NI")
        (field (name "PCB FOOTPRINT") "0603")
        (field (name "POWER") "0.25W")
      )
      (libsource (lib "Full") (part "Res0.3"))
    )
    (comp (ref "R78")
      (value "1K")
      (footprint "res 0603")
      (description "RES SMD,1K OHM,5%,1/10W,0603")
      (fields
        (field (name "MANUFACTURER1_PART#") "RMCF06031K00JNEAC")
        (field (name "MANUFACTURER2_PART#") "R0603J1KTG")
        (field (name "NI_MARK") "NI")
        (field (name "PCB FOOTPRINT") "0603")
        (field (name "POWER") "0.25W")
      )
      (libsource (lib "Full") (part "Res0.3"))
    )
    (comp (ref "R81")
      (value "5.1K")
      (footprint "res 0603")
      (description "RES SMD 5.1K OHM 1% 1/10W 0603")
      (fields (field (name "MANUFACTURER1_PART#") "RC0603FR-075K1L") (field (name "PCB FOOTPRINT") "0603"))
      (libsource (lib "Full") (part "Res0.3"))
    )
    (comp (ref "R82")
      (value "5.1K")
      (footprint "res 0603")
      (description "RES SMD 5.1K OHM 1% 1/10W 0603")
      (fields (field (name "MANUFACTURER1_PART#") "RC0603FR-075K1L") (field (name "PCB FOOTPRINT") "0603"))
      (libsource (lib "Full") (part "Res0.3"))
    )
    (comp (ref "R87")
      (value "1K")
      (footprint "res 0603")
      (description "RES SMD,1K OHM,5%,1/10W,0603")
      (fields
        (field (name "MANUFACTURER1_PART#") "RMCF06031K00JNEAC")
        (field (name "MANUFACTURER2_PART#") "R0603J1KTG")
        (field (name "NI_MARK") "NI")
        (field (name "PCB FOOTPRINT") "0603")
        (field (name "POWER") "0.25W")
      )
      (libsource (lib "Full") (part "Res0.3"))
    )
    (comp (ref "R88")
      (value "1K")
      (footprint "res 0603")
      (description "RES SMD,1K OHM,5%,1/10W,0603")
      (fields
        (field (name "MANUFACTURER1_PART#") "RMCF06031K00JNEAC")
        (field (name "MANUFACTURER2_PART#") "R0603J1KTG")
        (field (name "NI_MARK") "NI")
        (field (name "PCB FOOTPRINT") "0603")
        (field (name "POWER") "0.25W")
      )
      (libsource (lib "Full") (part "Res0.3"))
    )
    (comp (ref "R89")
      (value "1K")
      (footprint "res 0603")
      (description "RES SMD,1K OHM,5%,1/10W,0603")
      (fields
        (field (name "MANUFACTURER1_PART#") "RMCF06031K00JNEAC")
        (field (name "MANUFACTURER2_PART#") "R0603J1KTG")
        (field (name "NI_MARK") "NI")
        (field (name "PCB FOOTPRINT") "0603")
        (field (name "POWER") "0.25W")
      )
      (libsource (lib "Full") (part "Res0.3"))
    )
    (comp (ref "R119")
      (value "10K")
      (footprint "res 0603")
      (description "RES SMD,10K OHM 5% 1/10W 0603")
      (fields
        (field (name "MANUFACTURER1_PART#") "RMCF0603JT10K0")
        (field (name "MANUFACTURER2_PART#") "R0603J10KKDX")
        (field (name "PCB FOOTPRINT") "0603")
      )
      (libsource (lib "altium-import") (part "root_0_Res0.3_"))
    )
    (comp (ref "R120")
      (value "1K")
      (footprint "res 0603")
      (description "RES SMD,1K OHM,5%,1/10W,0603")
      (fields
        (field (name "MANUFACTURER1_PART#") "RMCF06031K00JNEAC")
        (field (name "MANUFACTURER2_PART#") "R0603J1KTG")
        (field (name "PCB FOOTPRINT") "0603")
      )
      (libsource (lib "Full") (part "Res0.3"))
    )
    (comp (ref "R121")
      (value "470R")
      (footprint "res 0603")
      (description "RES SMD, 470 OHM 5% 1/8W 0603")
      (fields
        (field (name "MANUFACTURER1_PART#") "RK73B1JTTD471J")
        (field (name "MANUFACTURER2_PART#") "RMCF0603JT470R")
      )
      (libsource (lib "Full") (part "Res0.3"))
    )
    (comp (ref "R122")
      (value "1K")
      (footprint "res 0603")
      (description "RES SMD,1K OHM,5%,1/10W,0603")
      (fields
        (field (name "MANUFACTURER1_PART#") "RMCF06031K00JNEAC")
        (field (name "MANUFACTURER2_PART#") "R0603J1KTG")
        (field (name "PCB FOOTPRINT") "0603")
      )
      (libsource (lib "Full") (part "Res0.3"))
    )
    (comp (ref "R123")
      (value "1K")
      (footprint "res 0603")
      (description "RES SMD,1K OHM,5%,1/10W,0603")
      (fields
        (field (name "MANUFACTURER1_PART#") "RMCF06031K00JNEAC")
        (field (name "MANUFACTURER2_PART#") "R0603J1KTG")
        (field (name "PCB FOOTPRINT") "0603")
      )
      (libsource (lib "Full") (part "Res0.3"))
    )
    (comp (ref "R124")
      (value "10K")
      (footprint "res 0603")
      (description "RES SMD,10K OHM 5% 1/10W 0603")
      (fields
        (field (name "MANUFACTURER1_PART#") "RMCF0603JT10K0")
        (field (name "MANUFACTURER2_PART#") "R0603J10KKDX")
        (field (name "PCB FOOTPRINT") "0603")
      )
      (libsource (lib "altium-import") (part "root_0_Res0.3_"))
    )
    (comp (ref "R125")
      (value "470R")
      (footprint "res 0603")
      (description "RES SMD, 470 OHM 5% 1/8W 0603")
      (fields
        (field (name "MANUFACTURER1_PART#") "RK73B1JTTD471J")
        (field (name "MANUFACTURER2_PART#") "RMCF0603JT470R")
      )
      (libsource (lib "Full") (part "Res0.3"))
    )
    (comp (ref "R126")
      (value "1K")
      (footprint "res 0603")
      (description "RES SMD,1K OHM,5%,1/10W,0603")
      (fields
        (field (name "MANUFACTURER1_PART#") "RMCF06031K00JNEAC")
        (field (name "MANUFACTURER2_PART#") "R0603J1KTG")
        (field (name "PCB FOOTPRINT") "0603")
      )
      (libsource (lib "Full") (part "Res0.3"))
    )
    (comp (ref "R127")
      (value "0.05R")
      (footprint "res 2512")
      (description "RES SMD 0.05 OHM 1% 1W 2512")
      (fields
        (field (name "MANUFACTURER1_PART#") "TLRP3A30CR050FTE")
        (field (name "MANUFACTURER2_PART#") "https://banlinhkien.com/tro-2512-1-r0500.05r-1w-p6652906.html")
        (field (name "PCB FOOTPRINT") "2512")
      )
      (libsource (lib "Full") (part "Res0.3"))
    )
    (comp (ref "R128")
      (value "0.05R")
      (footprint "res 2512")
      (description "RES SMD 0.05 OHM 1% 1W 2512")
      (fields
        (field (name "MANUFACTURER1_PART#") "TLRP3A30CR050FTE")
        (field (name "MANUFACTURER2_PART#") "https://banlinhkien.com/tro-2512-1-r0500.05r-1w-p6652906.html")
        (field (name "PCB FOOTPRINT") "2512")
      )
      (libsource (lib "Full") (part "Res0.3"))
    )
    (comp (ref "R133")
      (value "100R")
      (footprint "res 0603")
      (description "RES 100 OHM 5% 1/10W 0603")
      (fields (field (name "MANUFACTURER1_PART#") "RMCF0603JG100R") (field (name "PCB_ FOOTPRINT") "0603"))
      (libsource (lib "thuvien") (part "RES 120 OHM 5% 1/10W 0603"))
    )
    (comp (ref "R134")
      (value "100R")
      (footprint "res 0603")
      (description "RES 100 OHM 5% 1/10W 0603")
      (fields (field (name "MANUFACTURER1_PART#") "RMCF0603JG100R") (field (name "PCB_ FOOTPRINT") "0603"))
      (libsource (lib "thuvien") (part "RES 120 OHM 5% 1/10W 0603"))
    )
    (comp (ref "R135")
      (value "100R")
      (footprint "res 0603")
      (description "RES 100 OHM 5% 1/10W 0603")
      (fields (field (name "MANUFACTURER1_PART#") "RMCF0603JG100R") (field (name "PCB_ FOOTPRINT") "0603"))
      (libsource (lib "thuvien") (part "RES 120 OHM 5% 1/10W 0603"))
    )
    (comp (ref "R136")
      (value "100R")
      (footprint "res 0603")
      (description "RES 100 OHM 5% 1/10W 0603")
      (fields (field (name "MANUFACTURER1_PART#") "RMCF0603JG100R") (field (name "PCB_ FOOTPRINT") "0603"))
      (libsource (lib "thuvien") (part "RES 120 OHM 5% 1/10W 0603"))
    )
    (comp (ref "U4")
      (value "TPS54302DDCR")
      (footprint "SOT23-6")
      (description "IC REG BUCK ADJ 3A TSOT23-6,TPS54302DDCR")
      (fields
        (field (name "DISTR1_PART#") "296-46237-1-ND")
        (field (name "PACKAGE") "TSOT23-6")
        (field (name "BY") "VINFAST_RD")
      )
      (libsource (lib "*") (part "IC_TPS54302DDCR"))
    )
    (comp (ref "U8")
      (value "LM358BIDGKR")
      (footprint "SOIC-8")
      (description "IC OPAMP GP 2 CIRCUIT 8SOIC")
      (fields
        (field (name "MANUFACTURER1_PART#") "LM358BAIDR")
        (field (name "MANUFACTURER2_PART#") "LM358DR2G")
      )
      (libsource (lib "VSM") (part "LM358"))
    )
  )
  (nets
    (net (code "1") (name "+24V_SYS") (class "Default")
      (node (ref "D13") (pin "2") (pinfunction "K_2") (pintype "passive"))
      (node (ref "D14") (pin "2") (pinfunction "K_2") (pintype "passive"))
      (node (ref "D15") (pin "2") (pinfunction "K_2") (pintype "passive"))
      (node (ref "D19") (pin "2") (pinfunction "K_2") (pintype "passive"))
      (node (ref "D20") (pin "2") (pinfunction "K_2") (pintype "passive"))
      (node (ref "D21") (pin "2") (pinfunction "K_2") (pintype "passive"))
      (node (ref "K1") (pin "2") (pinfunction "COIL_1_2") (pintype "passive"))
      (node (ref "K2") (pin "2") (pinfunction "COIL_1_2") (pintype "passive"))
      (node (ref "K3") (pin "2") (pinfunction "COIL_1_2") (pintype "passive"))
      (node (ref "K4") (pin "2") (pinfunction "COIL_1_2") (pintype "passive"))
      (node (ref "K5") (pin "2") (pinfunction "COIL_1_2") (pintype "passive"))
      (node (ref "K6") (pin "2") (pinfunction "COIL_1_2") (pintype "passive"))
      (node (ref "L5") (pin "1") (pinfunction "1_1") (pintype "passive"))
      (node (ref "P10") (pin "3") (pinfunction "3_3") (pintype "passive"))
      (node (ref "P2") (pin "4") (pinfunction "4_4") (pintype "passive"))
      (node (ref "P3") (pin "1") (pinfunction "1_1") (pintype "passive"))
      (node (ref "P3") (pin "2") (pinfunction "2_2") (pintype "passive"))
      (node (ref "P3") (pin "3") (pinfunction "3_3") (pintype "passive"))
      (node (ref "P7") (pin "3") (pinfunction "3_3") (pintype "passive"))
      (node (ref "Q11") (pin "3") (pinfunction "S_3") (pintype "passive"))
      (node (ref "Q5") (pin "3") (pinfunction "S_3") (pintype "passive"))
      (node (ref "Q8") (pin "3") (pinfunction "S_3") (pintype "passive"))
      (node (ref "R45") (pin "1") (pinfunction "1_1") (pintype "passive"))
      (node (ref "R57") (pin "1") (pinfunction "1_1") (pintype "passive"))
      (node (ref "R62") (pin "1") (pinfunction "1_1") (pintype "passive"))
    )
    (net (code "2") (name "/COL1") (class "Default")
      (node (ref "P1") (pin "1") (pinfunction "1_1") (pintype "passive"))
      (node (ref "R29") (pin "2") (pinfunction "2_2") (pintype "passive"))
    )
    (net (code "3") (name "/COL2") (class "Default")
      (node (ref "P1") (pin "3") (pinfunction "3_3") (pintype "passive"))
      (node (ref "R32") (pin "2") (pinfunction "2_2") (pintype "passive"))
    )
    (net (code "4") (name "/COL3") (class "Default")
      (node (ref "P1") (pin "5") (pinfunction "5_5") (pintype "passive"))
      (node (ref "R33") (pin "2") (pinfunction "2_2") (pintype "passive"))
    )
    (net (code "5") (name "/COL4") (class "Default")
      (node (ref "P1") (pin "7") (pinfunction "7_7") (pintype "passive"))
      (node (ref "R34") (pin "2") (pinfunction "2_2") (pintype "passive"))
    )
    (net (code "6") (name "/Conveyer_motor") (class "Default")
      (node (ref "R50") (pin "2") (pinfunction "2_2") (pintype "passive"))
    )
    (net (code "7") (name "/DHT21") (class "Default")
      (node (ref "J7") (pin "2") (pinfunction "2_2") (pintype "passive"))
      (node (ref "R15") (pin "1") (pinfunction "1_1") (pintype "passive"))
    )
    (net (code "8") (name "/DOOR") (class "Default")
      (node (ref "P2") (pin "1") (pinfunction "1_1") (pintype "passive"))
      (node (ref "R18") (pin "1") (pinfunction "1_1") (pintype "passive"))
    )
    (net (code "9") (name "/DROP") (class "Default")
      (node (ref "P10") (pin "4") (pinfunction "4_4") (pintype "passive"))
      (node (ref "R20") (pin "1") (pinfunction "1_1") (pintype "passive"))
    )
    (net (code "10") (name "/EMPTY") (class "Default")
      (node (ref "P7") (pin "4") (pinfunction "4_4") (pintype "passive"))
      (node (ref "R27") (pin "1") (pinfunction "1_1") (pintype "passive"))
    )
    (net (code "11") (name "/GND_SWap_motor") (class "Default")
      (node (ref "C86") (pin "1") (pinfunction "1_1") (pintype "passive"))
      (node (ref "D26") (pin "1") (pinfunction "A_1") (pintype "passive"))
      (node (ref "P7") (pin "5") (pinfunction "5_5") (pintype "passive"))
      (node (ref "R126") (pin "2") (pinfunction "2_2") (pintype "passive"))
      (node (ref "R128") (pin "1") (pinfunction "1_1") (pintype "passive"))
    )
    (net (code "12") (name "/GND_motor") (class "Default")
      (node (ref "C85") (pin "1") (pinfunction "1_1") (pintype "passive"))
      (node (ref "D25") (pin "1") (pinfunction "A_1") (pintype "passive"))
      (node (ref "P10") (pin "5") (pinfunction "5_5") (pintype "passive"))
      (node (ref "R122") (pin "2") (pinfunction "2_2") (pintype "passive"))
      (node (ref "R127") (pin "1") (pinfunction "1_1") (pintype "passive"))
    )
    (net (code "13") (name "/Heater") (class "Default")
      (node (ref "R76") (pin "2") (pinfunction "2_2") (pintype "passive"))
    )
    (net (code "14") (name "/Heater1") (class "Default")
      (node (ref "K1") (pin "3") (pinfunction "NO_3") (pintype "passive"))
      (node (ref "P9") (pin "2") (pinfunction "2_2") (pintype "passive"))
    )
    (net (code "15") (name "/Heater2") (class "Default")
      (node (ref "K1") (pin "1") (pinfunction "COM_1") (pintype "passive"))
      (node (ref "P9") (pin "1") (pinfunction "1_1") (pintype "passive"))
    )
    (net (code "16") (name "/INPUT1") (class "Default")
      (node (ref "J4") (pin "2") (pinfunction "2_2") (pintype "passive"))
      (node (ref "R65") (pin "1") (pinfunction "1_1") (pintype "passive"))
    )
    (net (code "17") (name "/INPUT2") (class "Default")
      (node (ref "J4") (pin "3") (pinfunction "3_3") (pintype "passive"))
      (node (ref "R70") (pin "1") (pinfunction "1_1") (pintype "passive"))
    )
    (net (code "18") (name "/INPUT3") (class "Default")
      (node (ref "J4") (pin "4") (pinfunction "4_4") (pintype "passive"))
      (node (ref "R75") (pin "1") (pinfunction "1_1") (pintype "passive"))
    )
    (net (code "19") (name "/INPUT4") (class "Default")
      (node (ref "J4") (pin "5") (pinfunction "5_5") (pintype "passive"))
      (node (ref "R66") (pin "1") (pinfunction "1_1") (pintype "passive"))
    )
    (net (code "20") (name "/INPUT5") (class "Default")
      (node (ref "J4") (pin "6") (pinfunction "6_6") (pintype "passive"))
      (node (ref "R72") (pin "1") (pinfunction "1_1") (pintype "passive"))
    )
    (net (code "21") (name "/IN_DOOR") (class "Default")
      (node (ref "C25") (pin "2") (pinfunction "2_2") (pintype "passive"))
      (node (ref "Q25") (pin "3") (pinfunction "C_3") (pintype "passive"))
      (node (ref "R6") (pin "2") (pinfunction "2_2") (pintype "passive"))
    )
    (net (code "22") (name "/IN_DROP") (class "Default")
      (node (ref "C26") (pin "2") (pinfunction "2_2") (pintype "passive"))
      (node (ref "Q26") (pin "3") (pinfunction "C_3") (pintype "passive"))
      (node (ref "R8") (pin "2") (pinfunction "2_2") (pintype "passive"))
    )
    (net (code "23") (name "/IN_EMPTY") (class "Default")
      (node (ref "C27") (pin "2") (pinfunction "2_2") (pintype "passive"))
      (node (ref "Q27") (pin "3") (pinfunction "C_3") (pintype "passive"))
      (node (ref "R22") (pin "2") (pinfunction "2_2") (pintype "passive"))
    )
    (net (code "24") (name "/I_M_SENSE") (class "Default")
      (node (ref "C81") (pin "1") (pinfunction "1_1") (pintype "passive"))
      (node (ref "R119") (pin "2") (pinfunction "2_2") (pintype "passive"))
      (node (ref "R121") (pin "1") (pinfunction "1_1") (pintype "passive"))
      (node (ref "U8") (pin "1") (pinfunction "OUT_1") (pintype "passive"))
    )
    (net (code "25") (name "/KP_COL1") (class "Default")
      (node (ref "R29") (pin "1") (pinfunction "1_1") (pintype "passive"))
    )
    (net (code "26") (name "/KP_COL2") (class "Default")
      (node (ref "R32") (pin "1") (pinfunction "1_1") (pintype "passive"))
    )
    (net (code "27") (name "/KP_COL3") (class "Default")
      (node (ref "R33") (pin "1") (pinfunction "1_1") (pintype "passive"))
    )
    (net (code "28") (name "/KP_COL4") (class "Default")
      (node (ref "R34") (pin "1") (pinfunction "1_1") (pintype "passive"))
    )
    (net (code "29") (name "/KP_ROW1") (class "Default")
      (node (ref "R35") (pin "1") (pinfunction "1_1") (pintype "passive"))
    )
    (net (code "30") (name "/KP_ROW2") (class "Default")
      (node (ref "R36") (pin "1") (pinfunction "1_1") (pintype "passive"))
    )
    (net (code "31") (name "/KP_ROW3") (class "Default")
      (node (ref "R37") (pin "1") (pinfunction "1_1") (pintype "passive"))
    )
    (net (code "32") (name "/KP_ROW4") (class "Default")
      (node (ref "R38") (pin "1") (pinfunction "1_1") (pintype "passive"))
    )
    (net (code "33") (name "/LCD_CLK") (class "Default")
      (node (ref "HD1") (pin "6") (pinfunction "6_6") (pintype "passive"))
      (node (ref "R12") (pin "2") (pinfunction "2_2") (pintype "passive"))
    )
    (net (code "34") (name "/LCD_CS") (class "Default")
      (node (ref "HD1") (pin "4") (pinfunction "4_4") (pintype "passive"))
      (node (ref "R7") (pin "2") (pinfunction "2_2") (pintype "passive"))
    )
    (net (code "35") (name "/LCD_DI") (class "Default")
      (node (ref "HD1") (pin "5") (pinfunction "5_5") (pintype "passive"))
      (node (ref "R9") (pin "2") (pinfunction "2_2") (pintype "passive"))
    )
    (net (code "36") (name "/LCD_DO") (class "Default")
      (node (ref "HD1") (pin "8") (pinfunction "8_8") (pintype "passive"))
      (node (ref "R16") (pin "2") (pinfunction "2_2") (pintype "passive"))
    )
    (net (code "37") (name "/LCD_INT") (class "Default")
      (node (ref "HD1") (pin "7") (pinfunction "7_7") (pintype "passive"))
      (node (ref "R14") (pin "2") (pinfunction "2_2") (pintype "passive"))
    )
    (net (code "38") (name "/LCD_KLIGHT") (class "Default")
      (node (ref "HD1") (pin "20") (pinfunction "20_20") (pintype "passive"))
      (node (ref "R19") (pin "1") (pinfunction "1_1") (pintype "passive"))
    )
    (net (code "39") (name "/LCD_RST") (class "Default")
      (node (ref "HD1") (pin "17") (pinfunction "17_17") (pintype "passive"))
      (node (ref "R13") (pin "2") (pinfunction "2_2") (pintype "passive"))
    )
    (net (code "40") (name "/LCD_VDD") (class "Default")
      (node (ref "C24") (pin "2") (pinfunction "2_2") (pintype "passive"))
      (node (ref "HD1") (pin "19") (pinfunction "19_19") (pintype "passive"))
      (node (ref "HD1") (pin "2") (pinfunction "2_2") (pintype "passive"))
      (node (ref "L3") (pin "2") (pinfunction "2_2") (pintype "passive"))
    )
    (net (code "41") (name "/LED_1") (class "Default")
      (node (ref "R43") (pin "2") (pinfunction "2_2") (pintype "passive"))
    )
    (net (code "42") (name "/LED_2") (class "Default")
      (node (ref "R42") (pin "2") (pinfunction "2_2") (pintype "passive"))
    )
    (net (code "43") (name "/LED_3") (class "Default")
      (node (ref "R44") (pin "2") (pinfunction "2_2") (pintype "passive"))
    )
    (net (code "44") (name "/MCU_IN1") (class "Default")
      (node (ref "C41") (pin "2") (pinfunction "2_2") (pintype "passive"))
      (node (ref "Q28") (pin "3") (pinfunction "C_3") (pintype "passive"))
      (node (ref "R28") (pin "2") (pinfunction "2_2") (pintype "passive"))
    )
    (net (code "45") (name "/MCU_IN2") (class "Default")
      (node (ref "C43") (pin "2") (pinfunction "2_2") (pintype "passive"))
      (node (ref "Q30") (pin "3") (pinfunction "C_3") (pintype "passive"))
      (node (ref "R67") (pin "2") (pinfunction "2_2") (pintype "passive"))
    )
    (net (code "46") (name "/MCU_IN3") (class "Default")
      (node (ref "C45") (pin "2") (pinfunction "2_2") (pintype "passive"))
      (node (ref "Q32") (pin "3") (pinfunction "C_3") (pintype "passive"))
      (node (ref "R73") (pin "2") (pinfunction "2_2") (pintype "passive"))
    )
    (net (code "47") (name "/MCU_IN4") (class "Default")
      (node (ref "C42") (pin "2") (pinfunction "2_2") (pintype "passive"))
      (node (ref "Q29") (pin "3") (pinfunction "C_3") (pintype "passive"))
      (node (ref "R30") (pin "2") (pinfunction "2_2") (pintype "passive"))
    )
    (net (code "48") (name "/MCU_IN5") (class "Default")
      (node (ref "C44") (pin "2") (pinfunction "2_2") (pintype "passive"))
      (node (ref "Q31") (pin "3") (pinfunction "C_3") (pintype "passive"))
      (node (ref "R68") (pin "2") (pinfunction "2_2") (pintype "passive"))
    )
    (net (code "49") (name "/MCU_LCD_CLK") (class "Default")
      (node (ref "R12") (pin "1") (pinfunction "1_1") (pintype "passive"))
    )
    (net (code "50") (name "/MCU_LCD_CS") (class "Default")
      (node (ref "R7") (pin "1") (pinfunction "1_1") (pintype "passive"))
    )
    (net (code "51") (name "/MCU_LCD_DATA") (class "Default")
      (node (ref "R9") (pin "1") (pinfunction "1_1") (pintype "passive"))
    )
    (net (code "52") (name "/MCU_LCD_DO") (class "Default")
      (node (ref "R16") (pin "1") (pinfunction "1_1") (pintype "passive"))
    )
    (net (code "53") (name "/MCU_LCD_INT") (class "Default")
      (node (ref "R14") (pin "1") (pinfunction "1_1") (pintype "passive"))
    )
    (net (code "54") (name "/MCU_LCD_LIGHT") (class "Default")
      (node (ref "R25") (pin "2") (pinfunction "2_2") (pintype "passive"))
    )
    (net (code "55") (name "/MCU_LCD_RST") (class "Default")
      (node (ref "R13") (pin "1") (pinfunction "1_1") (pintype "passive"))
    )
    (net (code "56") (name "/MCU_MOTOR_CUR") (class "Default")
      (node (ref "C82") (pin "2") (pinfunction "2_2") (pintype "passive"))
      (node (ref "R121") (pin "2") (pinfunction "2_2") (pintype "passive"))
    )
    (net (code "57") (name "/MCU_MOTOR_SWAP_CUR_ADC") (class "Default")
      (node (ref "C84") (pin "2") (pinfunction "2_2") (pintype "passive"))
      (node (ref "R125") (pin "1") (pinfunction "1_1") (pintype "passive"))
    )
    (net (code "58") (name "/MCU_RELAY1") (class "Default")
      (node (ref "R87") (pin "2") (pinfunction "2_2") (pintype "passive"))
    )
    (net (code "59") (name "/MCU_RELAY2") (class "Default")
      (node (ref "R77") (pin "2") (pinfunction "2_2") (pintype "passive"))
    )
    (net (code "60") (name "/MCU_RELAY3") (class "Default")
      (node (ref "R88") (pin "2") (pinfunction "2_2") (pintype "passive"))
    )
    (net (code "61") (name "/MCU_RELAY4") (class "Default")
      (node (ref "R78") (pin "2") (pinfunction "2_2") (pintype "passive"))
    )
    (net (code "62") (name "/MCU_RELAY5") (class "Default")
      (node (ref "R89") (pin "2") (pinfunction "2_2") (pintype "passive"))
    )
    (net (code "63") (name "/MCU_RX_VADI") (class "Default")
      (node (ref "Q7") (pin "3") (pinfunction "C_3") (pintype "passive"))
      (node (ref "R55") (pin "2") (pinfunction "2_2") (pintype "passive"))
    )
    (net (code "64") (name "/MCU_TX_VADI") (class "Default")
      (node (ref "Q10") (pin "2") (pinfunction "E_2") (pintype "passive"))
    )
    (net (code "65") (name "/RELAY1_1") (class "Default")
      (node (ref "K4") (pin "3") (pinfunction "NO_3") (pintype "passive"))
      (node (ref "P8") (pin "6") (pinfunction "6_6") (pintype "passive"))
    )
    (net (code "66") (name "/RELAY1_2") (class "Default")
      (node (ref "K4") (pin "1") (pinfunction "COM_1") (pintype "passive"))
      (node (ref "P8") (pin "1") (pinfunction "1_1") (pintype "passive"))
    )
    (net (code "67") (name "/RELAY2_1") (class "Default")
      (node (ref "K2") (pin "3") (pinfunction "NO_3") (pintype "passive"))
      (node (ref "P8") (pin "7") (pinfunction "7_7") (pintype "passive"))
    )
    (net (code "68") (name "/RELAY2_2") (class "Default")
      (node (ref "K2") (pin "1") (pinfunction "COM_1") (pintype "passive"))
      (node (ref "P8") (pin "2") (pinfunction "2_2") (pintype "passive"))
    )
    (net (code "69") (name "/RELAY3_1") (class "Default")
      (node (ref "K5") (pin "3") (pinfunction "NO_3") (pintype "passive"))
      (node (ref "P8") (pin "8") (pinfunction "8_8") (pintype "passive"))
    )
    (net (code "70") (name "/RELAY3_2") (class "Default")
      (node (ref "K5") (pin "1") (pinfunction "COM_1") (pintype "passive"))
      (node (ref "P8") (pin "3") (pinfunction "3_3") (pintype "passive"))
    )
    (net (code "71") (name "/RELAY4_1") (class "Default")
      (node (ref "K3") (pin "3") (pinfunction "NO_3") (pintype "passive"))
      (node (ref "P8") (pin "9") (pinfunction "9_9") (pintype "passive"))
    )
    (net (code "72") (name "/RELAY4_2") (class "Default")
      (node (ref "K3") (pin "1") (pinfunction "COM_1") (pintype "passive"))
      (node (ref "P8") (pin "4") (pinfunction "4_4") (pintype "passive"))
    )
    (net (code "73") (name "/RELAY5_1") (class "Default")
      (node (ref "K6") (pin "3") (pinfunction "NO_3") (pintype "passive"))
      (node (ref "P8") (pin "10") (pinfunction "10_10") (pintype "passive"))
    )
    (net (code "74") (name "/RELAY5_2") (class "Default")
      (node (ref "K6") (pin "1") (pinfunction "COM_1") (pintype "passive"))
      (node (ref "P8") (pin "5") (pinfunction "5_5") (pintype "passive"))
    )
    (net (code "75") (name "/ROW1") (class "Default")
      (node (ref "C31") (pin "2") (pinfunction "2_2") (pintype "passive"))
      (node (ref "P1") (pin "2") (pinfunction "2_2") (pintype "passive"))
      (node (ref "R35") (pin "2") (pinfunction "2_2") (pintype "passive"))
    )
    (net (code "76") (name "/ROW2") (class "Default")
      (node (ref "C30") (pin "2") (pinfunction "2_2") (pintype "passive"))
      (node (ref "P1") (pin "4") (pinfunction "4_4") (pintype "passive"))
      (node (ref "R36") (pin "2") (pinfunction "2_2") (pintype "passive"))
    )
    (net (code "77") (name "/ROW3") (class "Default")
      (node (ref "C29") (pin "2") (pinfunction "2_2") (pintype "passive"))
      (node (ref "P1") (pin "6") (pinfunction "6_6") (pintype "passive"))
      (node (ref "R37") (pin "2") (pinfunction "2_2") (pintype "passive"))
    )
    (net (code "78") (name "/ROW4") (class "Default")
      (node (ref "C28") (pin "2") (pinfunction "2_2") (pintype "passive"))
      (node (ref "P1") (pin "8") (pinfunction "8_8") (pintype "passive"))
      (node (ref "R38") (pin "2") (pinfunction "2_2") (pintype "passive"))
    )
    (net (code "79") (name "/Solenoid") (class "Default")
      (node (ref "R63") (pin "2") (pinfunction "2_2") (pintype "passive"))
    )
    (net (code "80") (name "/Solenoid_out") (class "Default")
      (node (ref "D10") (pin "2") (pinfunction "K_2") (pintype "passive"))
      (node (ref "P10") (pin "1") (pinfunction "1_1") (pintype "passive"))
      (node (ref "Q11") (pin "2") (pinfunction "D_2") (pintype "passive"))
    )
    (net (code "81") (name "/Swap_motor") (class "Default")
      (node (ref "R61") (pin "2") (pinfunction "2_2") (pintype "passive"))
    )
    (net (code "82") (name "/TOUCH_INT") (class "Default")
      (node (ref "R136") (pin "1") (pinfunction "1_1") (pintype "passive"))
    )
    (net (code "83") (name "/TOUCH_RST") (class "Default")
      (node (ref "R135") (pin "1") (pinfunction "1_1") (pintype "passive"))
    )
    (net (code "84") (name "/T_INT") (class "Default")
      (node (ref "HD1") (pin "9") (pinfunction "9_9") (pintype "passive"))
      (node (ref "R136") (pin "2") (pinfunction "2_2") (pintype "passive"))
    )
    (net (code "85") (name "/T_RST") (class "Default")
      (node (ref "HD1") (pin "12") (pinfunction "12_12") (pintype "passive"))
      (node (ref "R135") (pin "2") (pinfunction "2_2") (pintype "passive"))
    )
    (net (code "86") (name "/T_SCL") (class "Default")
      (node (ref "HD1") (pin "10") (pinfunction "10_10") (pintype "passive"))
      (node (ref "R134") (pin "2") (pinfunction "2_2") (pintype "passive"))
    )
    (net (code "87") (name "/T_SDA") (class "Default")
      (node (ref "HD1") (pin "11") (pinfunction "11_11") (pintype "passive"))
      (node (ref "R133") (pin "2") (pinfunction "2_2") (pintype "passive"))
    )
    (net (code "88") (name "/VADI_RX") (class "Default")
      (node (ref "D9") (pin "1") (pinfunction "K_1") (pintype "passive"))
      (node (ref "P4") (pin "4") (pinfunction "4_4") (pintype "passive"))
      (node (ref "R60") (pin "2") (pinfunction "2_2") (pintype "passive"))
    )
    (net (code "89") (name "/VADI_TX") (class "Default")
      (node (ref "D9") (pin "2") (pinfunction "K_2") (pintype "passive"))
      (node (ref "P4") (pin "5") (pinfunction "5_5") (pintype "passive"))
      (node (ref "R59") (pin "2") (pinfunction "2_2") (pintype "passive"))
    )
    (net (code "90") (name "/V_SWap_motor") (class "Default")
      (node (ref "D8") (pin "2") (pinfunction "K_2") (pintype "passive"))
      (node (ref "P7") (pin "2") (pinfunction "2_2") (pintype "passive"))
      (node (ref "Q8") (pin "2") (pinfunction "D_2") (pintype "passive"))
    )
    (net (code "91") (name "/touch_scl") (class "Default")
      (node (ref "R134") (pin "1") (pinfunction "1_1") (pintype "passive"))
      (node (ref "R81") (pin "2") (pinfunction "2_2") (pintype "passive"))
    )
    (net (code "92") (name "/touch_sda") (class "Default")
      (node (ref "R133") (pin "1") (pinfunction "1_1") (pintype "passive"))
      (node (ref "R82") (pin "2") (pinfunction "2_2") (pintype "passive"))
    )
    (net (code "93") (name "3V3") (class "Default")
      (node (ref "C40") (pin "2") (pinfunction "2_2") (pintype "passive"))
      (node (ref "F2") (pin "1") (pinfunction "1_1") (pintype "passive"))
      (node (ref "J7") (pin "3") (pinfunction "3_3") (pintype "passive"))
      (node (ref "R10") (pin "2") (pinfunction "2_2") (pintype "passive"))
      (node (ref "R11") (pin "2") (pinfunction "2_2") (pintype "passive"))
      (node (ref "R15") (pin "2") (pinfunction "2_2") (pintype "passive"))
      (node (ref "R22") (pin "1") (pinfunction "1_1") (pintype "passive"))
      (node (ref "R23") (pin "2") (pinfunction "2_2") (pintype "passive"))
      (node (ref "R28") (pin "1") (pinfunction "1_1") (pintype "passive"))
      (node (ref "R30") (pin "1") (pinfunction "1_1") (pintype "passive"))
      (node (ref "R31") (pin "2") (pinfunction "2_2") (pintype "passive"))
      (node (ref "R55") (pin "1") (pinfunction "1_1") (pintype "passive"))
      (node (ref "R56") (pin "1") (pinfunction "1_1") (pintype "passive"))
      (node (ref "R6") (pin "1") (pinfunction "1_1") (pintype "passive"))
      (node (ref "R64") (pin "2") (pinfunction "2_2") (pintype "passive"))
      (node (ref "R67") (pin "1") (pinfunction "1_1") (pintype "passive"))
      (node (ref "R68") (pin "1") (pinfunction "1_1") (pintype "passive"))
      (node (ref "R69") (pin "2") (pinfunction "2_2") (pintype "passive"))
      (node (ref "R71") (pin "2") (pinfunction "2_2") (pintype "passive"))
      (node (ref "R73") (pin "1") (pinfunction "1_1") (pintype "passive"))
      (node (ref "R74") (pin "2") (pinfunction "2_2") (pintype "passive"))
      (node (ref "R8") (pin "1") (pinfunction "1_1") (pintype "passive"))
      (node (ref "R81") (pin "1") (pinfunction "1_1") (pintype "passive"))
      (node (ref "R82") (pin "1") (pinfunction "1_1") (pintype "passive"))
    )
    (net (code "94") (name "5V0") (class "Default")
      (node (ref "C39") (pin "1") (pinfunction "1_1") (pintype "passive"))
      (node (ref "C90") (pin "1") (pinfunction "1_1") (pintype "passive"))
      (node (ref "L3") (pin "1") (pinfunction "1_1") (pintype "passive"))
      (node (ref "R52") (pin "1") (pinfunction "1_1") (pintype "passive"))
      (node (ref "R54") (pin "1") (pinfunction "1_1") (pintype "passive"))
      (node (ref "R58") (pin "1") (pinfunction "1_1") (pintype "passive"))
      (node (ref "U8") (pin "8") (pinfunction "+V_8") (pintype "passive"))
    )
    (net (code "95") (name "12V_SYS") (class "Default")
      (node (ref "P4") (pin "3") (pinfunction "3_3") (pintype "passive"))
    )
    (net (code "96") (name "DGND") (class "Default")
      (node (ref "C24") (pin "1") (pinfunction "1_1") (pintype "passive"))
      (node (ref "C25") (pin "1") (pinfunction "1_1") (pintype "passive"))
      (node (ref "C26") (pin "1") (pinfunction "1_1") (pintype "passive"))
      (node (ref "C27") (pin "1") (pinfunction "1_1") (pintype "passive"))
      (node (ref "C28") (pin "1") (pinfunction "1_1") (pintype "passive"))
      (node (ref "C29") (pin "1") (pinfunction "1_1") (pintype "passive"))
      (node (ref "C30") (pin "1") (pinfunction "1_1") (pintype "passive"))
      (node (ref "C31") (pin "1") (pinfunction "1_1") (pintype "passive"))
      (node (ref "C32") (pin "1") (pinfunction "1_1") (pintype "passive"))
      (node (ref "C34") (pin "1") (pinfunction "1_1") (pintype "passive"))
      (node (ref "C35") (pin "2") (pinfunction "2_2") (pintype "passive"))
      (node (ref "C36") (pin "1") (pinfunction "1_1") (pintype "passive"))
      (node (ref "C37") (pin "1") (pinfunction "1_1") (pintype "passive"))
      (node (ref "C39") (pin "2") (pinfunction "2_2") (pintype "passive"))
      (node (ref "C40") (pin "1") (pinfunction "1_1") (pintype "passive"))
      (node (ref "C41") (pin "1") (pinfunction "1_1") (pintype "passive"))
      (node (ref "C42") (pin "1") (pinfunction "1_1") (pintype "passive"))
      (node (ref "C43") (pin "1") (pinfunction "1_1") (pintype "passive"))
      (node (ref "C44") (pin "1") (pinfunction "1_1") (pintype "passive"))
      (node (ref "C45") (pin "1") (pinfunction "1_1") (pintype "passive"))
      (node (ref "C76") (pin "1") (pinfunction "1_1") (pintype "passive"))
      (node (ref "C82") (pin "1") (pinfunction "1_1") (pintype "passive"))
      (node (ref "C84") (pin "1") (pinfunction "1_1") (pintype "passive"))
      (node (ref "C85") (pin "2") (pinfunction "2_2") (pintype "passive"))
      (node (ref "C86") (pin "2") (pinfunction "2_2") (pintype "passive"))
      (node (ref "C90") (pin "2") (pinfunction "2_2") (pintype "passive"))
      (node (ref "D10") (pin "1") (pinfunction "A_1") (pintype "passive"))
      (node (ref "D25") (pin "2") (pinfunction "K_2") (pintype "passive"))
      (node (ref "D26") (pin "2") (pinfunction "K_2") (pintype "passive"))
      (node (ref "D8") (pin "1") (pinfunction "A_1") (pintype "passive"))
      (node (ref "D9") (pin "3") (pinfunction "A_3") (pintype "passive"))
      (node (ref "HD1") (pin "1") (pinfunction "1_1") (pintype "passive"))
      (node (ref "J4") (pin "1") (pinfunction "1_1") (pintype "passive"))
      (node (ref "J7") (pin "1") (pinfunction "1_1") (pintype "passive"))
      (node (ref "P1") (pin "9") (pinfunction "9_9") (pintype "passive"))
      (node (ref "P10") (pin "6") (pinfunction "6_6") (pintype "passive"))
      (node (ref "P2") (pin "3") (pinfunction "3_3") (pintype "passive"))
      (node (ref "P4") (pin "2") (pinfunction "2_2") (pintype "passive"))
      (node (ref "P4") (pin "6") (pinfunction "6_6") (pintype "passive"))
      (node (ref "P7") (pin "6") (pinfunction "6_6") (pintype "passive"))
      (node (ref "Q1") (pin "2") (pinfunction "S_2") (pintype "passive"))
      (node (ref "Q12") (pin "2") (pinfunction "E_2") (pintype "passive"))
      (node (ref "Q13") (pin "2") (pinfunction "E_2") (pintype "passive"))
      (node (ref "Q14") (pin "2") (pinfunction "E_2") (pintype "passive"))
      (node (ref "Q15") (pin "2") (pinfunction "E_2") (pintype "passive"))
      (node (ref "Q16") (pin "2") (pinfunction "E_2") (pintype "passive"))
      (node (ref "Q17") (pin "2") (pinfunction "E_2") (pintype "passive"))
      (node (ref "Q18") (pin "2") (pinfunction "E_2") (pintype "passive"))
      (node (ref "Q2") (pin "2") (pinfunction "E_2") (pintype "passive"))
      (node (ref "Q25") (pin "2") (pinfunction "E_2") (pintype "passive"))
      (node (ref "Q26") (pin "2") (pinfunction "E_2") (pintype "passive"))
      (node (ref "Q27") (pin "2") (pinfunction "E_2") (pintype "passive"))
      (node (ref "Q28") (pin "2") (pinfunction "E_2") (pintype "passive"))
      (node (ref "Q29") (pin "2") (pinfunction "E_2") (pintype "passive"))
      (node (ref "Q3") (pin "2") (pinfunction "E_2") (pintype "passive"))
      (node (ref "Q30") (pin "2") (pinfunction "E_2") (pintype "passive"))
      (node (ref "Q31") (pin "2") (pinfunction "E_2") (pintype "passive"))
      (node (ref "Q32") (pin "2") (pinfunction "E_2") (pintype "passive"))
      (node (ref "Q4") (pin "2") (pinfunction "E_2") (pintype "passive"))
      (node (ref "Q6") (pin "2") (pinfunction "E_2") (pintype "passive"))
      (node (ref "Q9") (pin "2") (pinfunction "E_2") (pintype "passive"))
      (node (ref "R120") (pin "2") (pinfunction "2_2") (pintype "passive"))
      (node (ref "R123") (pin "2") (pinfunction "2_2") (pintype "passive"))
      (node (ref "R127") (pin "2") (pinfunction "2_2") (pintype "passive"))
      (node (ref "R128") (pin "2") (pinfunction "2_2") (pintype "passive"))
      (node (ref "R26") (pin "2") (pinfunction "2_2") (pintype "passive"))
      (node (ref "R49") (pin "1") (pinfunction "TOP_1") (pintype "passive"))
      (node (ref "R49") (pin "3") (pinfunction "TAP_3") (pintype "passive"))
      (node (ref "R51") (pin "2") (pinfunction "2_2") (pintype "passive"))
      (node (ref "R53") (pin "2") (pinfunction "2_2") (pintype "passive"))
      (node (ref "U4") (pin "1") (pinfunction "GND_1") (pintype "power_in"))
      (node (ref "U8") (pin "4") (pinfunction "-V_4") (pintype "passive"))
    )
    (net (code "97") (name "Net-(C32-Pad2)") (class "Default")
      (node (ref "C32") (pin "2") (pinfunction "2_2") (pintype "passive"))
      (node (ref "F2") (pin "2") (pinfunction "2_2") (pintype "passive"))
      (node (ref "P1") (pin "10") (pinfunction "10_10") (pintype "passive"))
    )
    (net (code "98") (name "Net-(D13-A)") (class "Default")
      (node (ref "D13") (pin "1") (pinfunction "A_1") (pintype "passive"))
      (node (ref "K1") (pin "5") (pinfunction "COIL_2_5") (pintype "passive"))
      (node (ref "Q13") (pin "3") (pinfunction "C_3") (pintype "passive"))
    )
    (net (code "99") (name "Net-(D14-A)") (class "Default")
      (node (ref "D14") (pin "1") (pinfunction "A_1") (pintype "passive"))
      (node (ref "K2") (pin "5") (pinfunction "COIL_2_5") (pintype "passive"))
      (node (ref "Q14") (pin "3") (pinfunction "C_3") (pintype "passive"))
    )
    (net (code "100") (name "Net-(D15-A)") (class "Default")
      (node (ref "D15") (pin "1") (pinfunction "A_1") (pintype "passive"))
      (node (ref "K3") (pin "5") (pinfunction "COIL_2_5") (pintype "passive"))
      (node (ref "Q15") (pin "3") (pinfunction "C_3") (pintype "passive"))
    )
    (net (code "101") (name "Net-(D19-A)") (class "Default")
      (node (ref "D19") (pin "1") (pinfunction "A_1") (pintype "passive"))
      (node (ref "K4") (pin "5") (pinfunction "COIL_2_5") (pintype "passive"))
      (node (ref "Q16") (pin "3") (pinfunction "C_3") (pintype "passive"))
    )
    (net (code "102") (name "Net-(D20-A)") (class "Default")
      (node (ref "D20") (pin "1") (pinfunction "A_1") (pintype "passive"))
      (node (ref "K5") (pin "5") (pinfunction "COIL_2_5") (pintype "passive"))
      (node (ref "Q17") (pin "3") (pinfunction "C_3") (pintype "passive"))
    )
    (net (code "103") (name "Net-(D21-A)") (class "Default")
      (node (ref "D21") (pin "1") (pinfunction "A_1") (pintype "passive"))
      (node (ref "K6") (pin "5") (pinfunction "COIL_2_5") (pintype "passive"))
      (node (ref "Q18") (pin "3") (pinfunction "C_3") (pintype "passive"))
    )
    (net (code "104") (name "Net-(L4-A)") (class "Default")
      (node (ref "C38") (pin "2") (pinfunction "2_2") (pintype "passive"))
      (node (ref "L4") (pin "1") (pinfunction "A_1") (pintype "passive"))
      (node (ref "U4") (pin "2") (pinfunction "SW_2") (pintype "output"))
    )
    (net (code "105") (name "Net-(L5-Pad2)") (class "Default")
      (node (ref "L5") (pin "2") (pinfunction "2_2") (pintype "passive"))
      (node (ref "P4") (pin "1") (pinfunction "1_1") (pintype "passive"))
    )
    (net (code "106") (name "Net-(P3-Pad4)") (class "Default")
      (node (ref "P3") (pin "4") (pinfunction "4_4") (pintype "passive"))
      (node (ref "R39") (pin "1") (pinfunction "1_1") (pintype "passive"))
    )
    (net (code "107") (name "Net-(P3-Pad5)") (class "Default")
      (node (ref "P3") (pin "5") (pinfunction "5_5") (pintype "passive"))
      (node (ref "R40") (pin "1") (pinfunction "1_1") (pintype "passive"))
    )
    (net (code "108") (name "Net-(P3-Pad6)") (class "Default")
      (node (ref "P3") (pin "6") (pinfunction "6_6") (pintype "passive"))
      (node (ref "R41") (pin "1") (pinfunction "1_1") (pintype "passive"))
    )
    (net (code "109") (name "Net-(Q1-D)") (class "Default")
      (node (ref "Q1") (pin "3") (pinfunction "D_3") (pintype "passive"))
      (node (ref "R19") (pin "2") (pinfunction "2_2") (pintype "passive"))
    )
    (net (code "110") (name "Net-(Q1-G)") (class "Default")
      (node (ref "Q1") (pin "1") (pinfunction "G_1") (pintype "passive"))
      (node (ref "R25") (pin "1") (pinfunction "1_1") (pintype "passive"))
      (node (ref "R26") (pin "1") (pinfunction "1_1") (pintype "passive"))
    )
    (net (code "111") (name "Net-(Q2-B)") (class "Default")
      (node (ref "Q2") (pin "1") (pinfunction "B_1") (pintype "passive"))
      (node (ref "R42") (pin "1") (pinfunction "1_1") (pintype "passive"))
    )
    (net (code "112") (name "Net-(Q2-C)") (class "Default")
      (node (ref "Q2") (pin "3") (pinfunction "C_3") (pintype "passive"))
      (node (ref "R40") (pin "2") (pinfunction "2_2") (pintype "passive"))
    )
    (net (code "113") (name "Net-(Q3-B)") (class "Default")
      (node (ref "Q3") (pin "1") (pinfunction "B_1") (pintype "passive"))
      (node (ref "R43") (pin "1") (pinfunction "1_1") (pintype "passive"))
    )
    (net (code "114") (name "Net-(Q3-C)") (class "Default")
      (node (ref "Q3") (pin "3") (pinfunction "C_3") (pintype "passive"))
      (node (ref "R39") (pin "2") (pinfunction "2_2") (pintype "passive"))
    )
    (net (code "115") (name "Net-(Q4-B)") (class "Default")
      (node (ref "Q4") (pin "1") (pinfunction "B_1") (pintype "passive"))
      (node (ref "R44") (pin "1") (pinfunction "1_1") (pintype "passive"))
    )
    (net (code "116") (name "Net-(Q4-C)") (class "Default")
      (node (ref "Q4") (pin "3") (pinfunction "C_3") (pintype "passive"))
      (node (ref "R41") (pin "2") (pinfunction "2_2") (pintype "passive"))
    )
    (net (code "117") (name "Net-(Q5-D)") (class "Default")
      (node (ref "C34") (pin "2") (pinfunction "2_2") (pintype "passive"))
      (node (ref "C76") (pin "2") (pinfunction "2_2") (pintype "passive"))
      (node (ref "Q5") (pin "2") (pinfunction "D_2") (pintype "passive"))
      (node (ref "R46") (pin "2") (pinfunction "2_2") (pintype "passive"))
      (node (ref "U4") (pin "3") (pinfunction "VIN_3") (pintype "power_in"))
    )
    (net (code "118") (name "Net-(Q5-G)") (class "Default")
      (node (ref "Q5") (pin "1") (pinfunction "G_1") (pintype "passive"))
      (node (ref "Q6") (pin "3") (pinfunction "C_3") (pintype "passive"))
      (node (ref "R45") (pin "2") (pinfunction "2_2") (pintype "passive"))
    )
    (net (code "119") (name "Net-(Q6-B)") (class "Default")
      (node (ref "Q6") (pin "1") (pinfunction "B_1") (pintype "passive"))
      (node (ref "R50") (pin "1") (pinfunction "1_1") (pintype "passive"))
    )
    (net (code "120") (name "Net-(Q7-B)") (class "Default")
      (node (ref "Q7") (pin "1") (pinfunction "B_1") (pintype "passive"))
      (node (ref "R52") (pin "2") (pinfunction "2_2") (pintype "passive"))
    )
    (net (code "121") (name "Net-(Q7-E)") (class "Default")
      (node (ref "Q7") (pin "2") (pinfunction "E_2") (pintype "passive"))
      (node (ref "R54") (pin "2") (pinfunction "2_2") (pintype "passive"))
      (node (ref "R59") (pin "1") (pinfunction "1_1") (pintype "passive"))
    )
    (net (code "122") (name "Net-(Q8-G)") (class "Default")
      (node (ref "Q8") (pin "1") (pinfunction "G_1") (pintype "passive"))
      (node (ref "Q9") (pin "3") (pinfunction "C_3") (pintype "passive"))
      (node (ref "R57") (pin "2") (pinfunction "2_2") (pintype "passive"))
    )
    (net (code "123") (name "Net-(Q9-B)") (class "Default")
      (node (ref "Q9") (pin "1") (pinfunction "B_1") (pintype "passive"))
      (node (ref "R61") (pin "1") (pinfunction "1_1") (pintype "passive"))
    )
    (net (code "124") (name "Net-(Q10-B)") (class "Default")
      (node (ref "Q10") (pin "1") (pinfunction "B_1") (pintype "passive"))
      (node (ref "R56") (pin "2") (pinfunction "2_2") (pintype "passive"))
    )
    (net (code "125") (name "Net-(Q10-C)") (class "Default")
      (node (ref "Q10") (pin "3") (pinfunction "C_3") (pintype "passive"))
      (node (ref "R58") (pin "2") (pinfunction "2_2") (pintype "passive"))
      (node (ref "R60") (pin "1") (pinfunction "1_1") (pintype "passive"))
    )
    (net (code "126") (name "Net-(Q11-G)") (class "Default")
      (node (ref "Q11") (pin "1") (pinfunction "G_1") (pintype "passive"))
      (node (ref "Q12") (pin "3") (pinfunction "C_3") (pintype "passive"))
      (node (ref "R62") (pin "2") (pinfunction "2_2") (pintype "passive"))
    )
    (net (code "127") (name "Net-(Q12-B)") (class "Default")
      (node (ref "Q12") (pin "1") (pinfunction "B_1") (pintype "passive"))
      (node (ref "R63") (pin "1") (pinfunction "1_1") (pintype "passive"))
    )
    (net (code "128") (name "Net-(Q13-B)") (class "Default")
      (node (ref "Q13") (pin "1") (pinfunction "B_1") (pintype "passive"))
      (node (ref "R76") (pin "1") (pinfunction "1_1") (pintype "passive"))
    )
    (net (code "129") (name "Net-(Q14-B)") (class "Default")
      (node (ref "Q14") (pin "1") (pinfunction "B_1") (pintype "passive"))
      (node (ref "R77") (pin "1") (pinfunction "1_1") (pintype "passive"))
    )
    (net (code "130") (name "Net-(Q15-B)") (class "Default")
      (node (ref "Q15") (pin "1") (pinfunction "B_1") (pintype "passive"))
      (node (ref "R78") (pin "1") (pinfunction "1_1") (pintype "passive"))
    )
    (net (code "131") (name "Net-(Q16-B)") (class "Default")
      (node (ref "Q16") (pin "1") (pinfunction "B_1") (pintype "passive"))
      (node (ref "R87") (pin "1") (pinfunction "1_1") (pintype "passive"))
    )
    (net (code "132") (name "Net-(Q17-B)") (class "Default")
      (node (ref "Q17") (pin "1") (pinfunction "B_1") (pintype "passive"))
      (node (ref "R88") (pin "1") (pinfunction "1_1") (pintype "passive"))
    )
    (net (code "133") (name "Net-(Q18-B)") (class "Default")
      (node (ref "Q18") (pin "1") (pinfunction "B_1") (pintype "passive"))
      (node (ref "R89") (pin "1") (pinfunction "1_1") (pintype "passive"))
    )
    (net (code "134") (name "Net-(Q25-B)") (class "Default")
      (node (ref "Q25") (pin "1") (pinfunction "B_1") (pintype "passive"))
      (node (ref "R10") (pin "1") (pinfunction "1_1") (pintype "passive"))
      (node (ref "R18") (pin "2") (pinfunction "2_2") (pintype "passive"))
    )
    (net (code "135") (name "Net-(Q26-B)") (class "Default")
      (node (ref "Q26") (pin "1") (pinfunction "B_1") (pintype "passive"))
      (node (ref "R11") (pin "1") (pinfunction "1_1") (pintype "passive"))
      (node (ref "R20") (pin "2") (pinfunction "2_2") (pintype "passive"))
    )
    (net (code "136") (name "Net-(Q27-B)") (class "Default")
      (node (ref "Q27") (pin "1") (pinfunction "B_1") (pintype "passive"))
      (node (ref "R23") (pin "1") (pinfunction "1_1") (pintype "passive"))
      (node (ref "R27") (pin "2") (pinfunction "2_2") (pintype "passive"))
    )
    (net (code "137") (name "Net-(Q28-B)") (class "Default")
      (node (ref "Q28") (pin "1") (pinfunction "B_1") (pintype "passive"))
      (node (ref "R31") (pin "1") (pinfunction "1_1") (pintype "passive"))
      (node (ref "R65") (pin "2") (pinfunction "2_2") (pintype "passive"))
    )
    (net (code "138") (name "Net-(Q29-B)") (class "Default")
      (node (ref "Q29") (pin "1") (pinfunction "B_1") (pintype "passive"))
      (node (ref "R64") (pin "1") (pinfunction "1_1") (pintype "passive"))
      (node (ref "R66") (pin "2") (pinfunction "2_2") (pintype "passive"))
    )
    (net (code "139") (name "Net-(Q30-B)") (class "Default")
      (node (ref "Q30") (pin "1") (pinfunction "B_1") (pintype "passive"))
      (node (ref "R69") (pin "1") (pinfunction "1_1") (pintype "passive"))
      (node (ref "R70") (pin "2") (pinfunction "2_2") (pintype "passive"))
    )
    (net (code "140") (name "Net-(Q31-B)") (class "Default")
      (node (ref "Q31") (pin "1") (pinfunction "B_1") (pintype "passive"))
      (node (ref "R71") (pin "1") (pinfunction "1_1") (pintype "passive"))
      (node (ref "R72") (pin "2") (pinfunction "2_2") (pintype "passive"))
    )
    (net (code "141") (name "Net-(Q32-B)") (class "Default")
      (node (ref "Q32") (pin "1") (pinfunction "B_1") (pintype "passive"))
      (node (ref "R74") (pin "1") (pinfunction "1_1") (pintype "passive"))
      (node (ref "R75") (pin "2") (pinfunction "2_2") (pintype "passive"))
    )
    (net (code "142") (name "Net-(R49-BOT)") (class "Default")
      (node (ref "R48") (pin "2") (pinfunction "2_2") (pintype "passive"))
      (node (ref "R49") (pin "2") (pinfunction "BOT_2") (pintype "passive"))
    )
    (net (code "143") (name "Net-(U4-EN)") (class "Default")
      (node (ref "R46") (pin "1") (pinfunction "1_1") (pintype "passive"))
      (node (ref "R51") (pin "1") (pinfunction "1_1") (pintype "passive"))
      (node (ref "U4") (pin "5") (pinfunction "EN_5") (pintype "input"))
    )
    (net (code "144") (name "Net-(U4-VBST)") (class "Default")
      (node (ref "C38") (pin "1") (pinfunction "1_1") (pintype "passive"))
      (node (ref "U4") (pin "6") (pinfunction "VBST_6") (pintype "output"))
    )
    (net (code "145") (name "Net-(U4-VFB)") (class "Default")
      (node (ref "R47") (pin "1") (pinfunction "1_1") (pintype "passive"))
      (node (ref "R48") (pin "1") (pinfunction "1_1") (pintype "passive"))
      (node (ref "R53") (pin "1") (pinfunction "1_1") (pintype "passive"))
      (node (ref "U4") (pin "4") (pinfunction "VFB_4") (pintype "input"))
    )
    (net (code "146") (name "Net-(U8A-IN+)") (class "Default")
      (node (ref "R122") (pin "1") (pinfunction "1_1") (pintype "passive"))
      (node (ref "U8") (pin "3") (pinfunction "IN+_3") (pintype "passive"))
    )
    (net (code "147") (name "Net-(U8A-IN-)") (class "Default")
      (node (ref "C81") (pin "2") (pinfunction "2_2") (pintype "passive"))
      (node (ref "R119") (pin "1") (pinfunction "1_1") (pintype "passive"))
      (node (ref "R120") (pin "1") (pinfunction "1_1") (pintype "passive"))
      (node (ref "U8") (pin "2") (pinfunction "IN-_2") (pintype "passive"))
    )
    (net (code "148") (name "Net-(U8B-IN+)") (class "Default")
      (node (ref "R126") (pin "1") (pinfunction "1_1") (pintype "passive"))
      (node (ref "U8") (pin "5") (pinfunction "IN+_5") (pintype "passive"))
    )
    (net (code "149") (name "Net-(U8B-IN-)") (class "Default")
      (node (ref "C83") (pin "2") (pinfunction "2_2") (pintype "passive"))
      (node (ref "R123") (pin "1") (pinfunction "1_1") (pintype "passive"))
      (node (ref "R124") (pin "1") (pinfunction "1_1") (pintype "passive"))
      (node (ref "U8") (pin "6") (pinfunction "IN-_6") (pintype "passive"))
    )
    (net (code "150") (name "Net-(U8B-OUT)") (class "Default")
      (node (ref "C83") (pin "1") (pinfunction "1_1") (pintype "passive"))
      (node (ref "R124") (pin "2") (pinfunction "2_2") (pintype "passive"))
      (node (ref "R125") (pin "2") (pinfunction "2_2") (pintype "passive"))
      (node (ref "U8") (pin "7") (pinfunction "OUT_7") (pintype "passive"))
    )
    (net (code "151") (name "V_motor") (class "Default")
      (node (ref "C35") (pin "1") (pinfunction "1_1") (pintype "passive"))
      (node (ref "C36") (pin "2") (pinfunction "2_2") (pintype "passive"))
      (node (ref "C37") (pin "2") (pinfunction "2_2") (pintype "passive"))
      (node (ref "L4") (pin "2") (pinfunction "B_2") (pintype "passive"))
      (node (ref "P10") (pin "2") (pinfunction "2_2") (pintype "passive"))
      (node (ref "R47") (pin "2") (pinfunction "2_2") (pintype "passive"))
    )
    (net (code "152") (name "unconnected-(HD1-Pad3)") (class "Default")
      (node (ref "HD1") (pin "3") (pinfunction "3_3") (pintype "passive+no_connect"))
    )
    (net (code "153") (name "unconnected-(HD1-Pad13)") (class "Default")
      (node (ref "HD1") (pin "13") (pinfunction "13_13") (pintype "passive+no_connect"))
    )
    (net (code "154") (name "unconnected-(HD1-Pad14)") (class "Default")
      (node (ref "HD1") (pin "14") (pinfunction "14_14") (pintype "passive+no_connect"))
    )
    (net (code "155") (name "unconnected-(HD1-Pad15)") (class "Default")
      (node (ref "HD1") (pin "15") (pinfunction "15_15") (pintype "passive+no_connect"))
    )
    (net (code "156") (name "unconnected-(HD1-Pad16)") (class "Default")
      (node (ref "HD1") (pin "16") (pinfunction "16_16") (pintype "passive+no_connect"))
    )
    (net (code "157") (name "unconnected-(HD1-Pad18)") (class "Default")
      (node (ref "HD1") (pin "18") (pinfunction "18_18") (pintype "passive+no_connect"))
    )
    (net (code "158") (name "unconnected-(K1-NC-Pad4)") (class "Default")
      (node (ref "K1") (pin "4") (pinfunction "NC_4") (pintype "passive"))
    )
    (net (code "159") (name "unconnected-(K2-NC-Pad4)") (class "Default")
      (node (ref "K2") (pin "4") (pinfunction "NC_4") (pintype "passive"))
    )
    (net (code "160") (name "unconnected-(K3-NC-Pad4)") (class "Default")
      (node (ref "K3") (pin "4") (pinfunction "NC_4") (pintype "passive"))
    )
    (net (code "161") (name "unconnected-(K4-NC-Pad4)") (class "Default")
      (node (ref "K4") (pin "4") (pinfunction "NC_4") (pintype "passive"))
    )
    (net (code "162") (name "unconnected-(K5-NC-Pad4)") (class "Default")
      (node (ref "K5") (pin "4") (pinfunction "NC_4") (pintype "passive"))
    )
    (net (code "163") (name "unconnected-(K6-NC-Pad4)") (class "Default")
      (node (ref "K6") (pin "4") (pinfunction "NC_4") (pintype "passive"))
    )
    (net (code "164") (name "unconnected-(P2-Pad2)") (class "Default")
      (node (ref "P2") (pin "2") (pinfunction "2_2") (pintype "passive"))
    )
    (net (code "165") (name "unconnected-(P2-Pad5)") (class "Default")
      (node (ref "P2") (pin "5") (pinfunction "5_5") (pintype "passive"))
    )
    (net (code "166") (name "unconnected-(P2-Pad6)") (class "Default")
      (node (ref "P2") (pin "6") (pinfunction "6_6") (pintype "passive"))
    )
    (net (code "167") (name "unconnected-(P7-Pad1)") (class "Default")
      (node (ref "P7") (pin "1") (pinfunction "1_1") (pintype "passive+no_connect"))
    )
  )
)
